# L3DCube_6x6x6_BaseBoard_Rev1_2.net
KiCad netlist of a schematic drawn in EAGLE
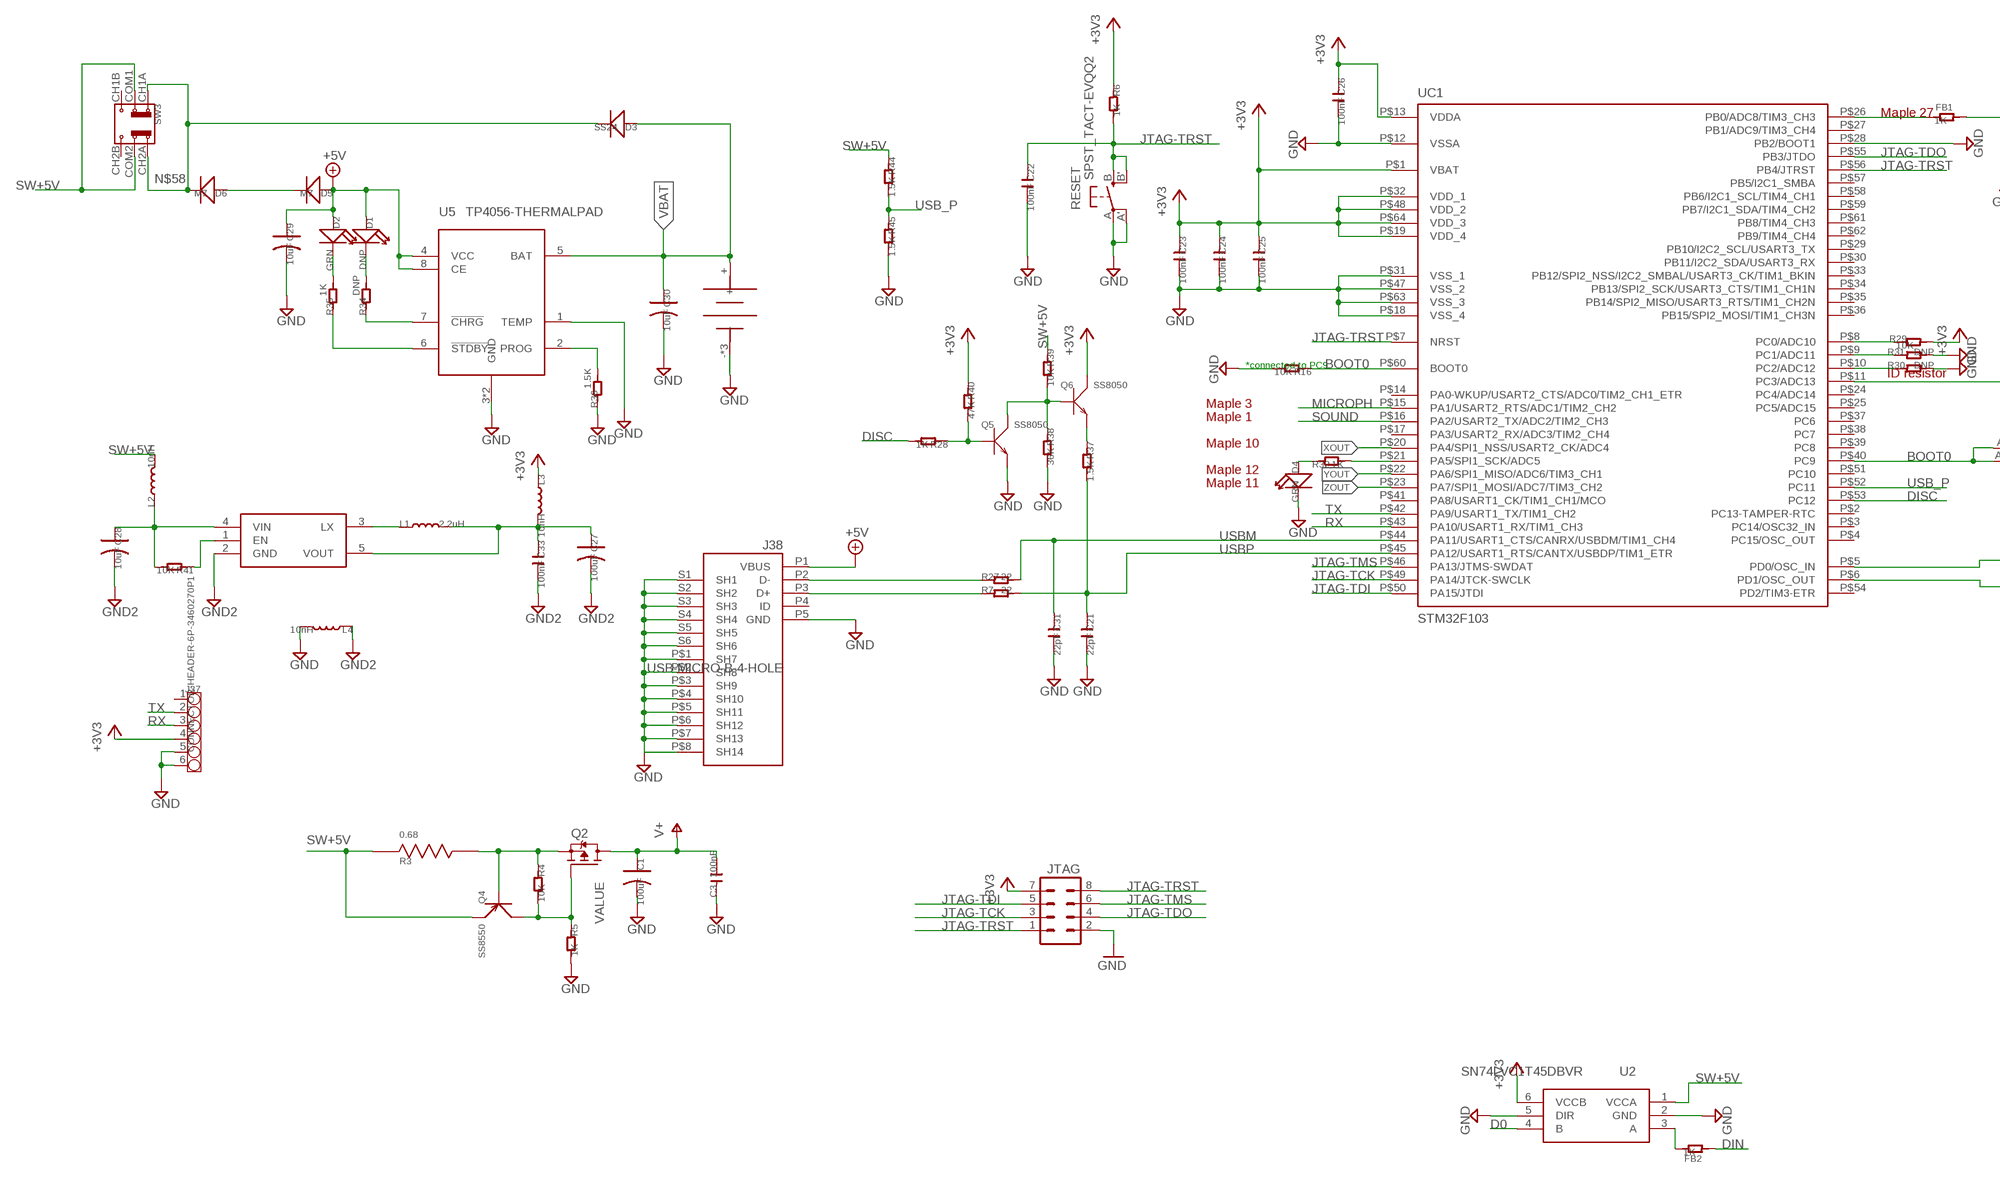
[diagram p0: schematic, sheet 1, part 1 of 2]
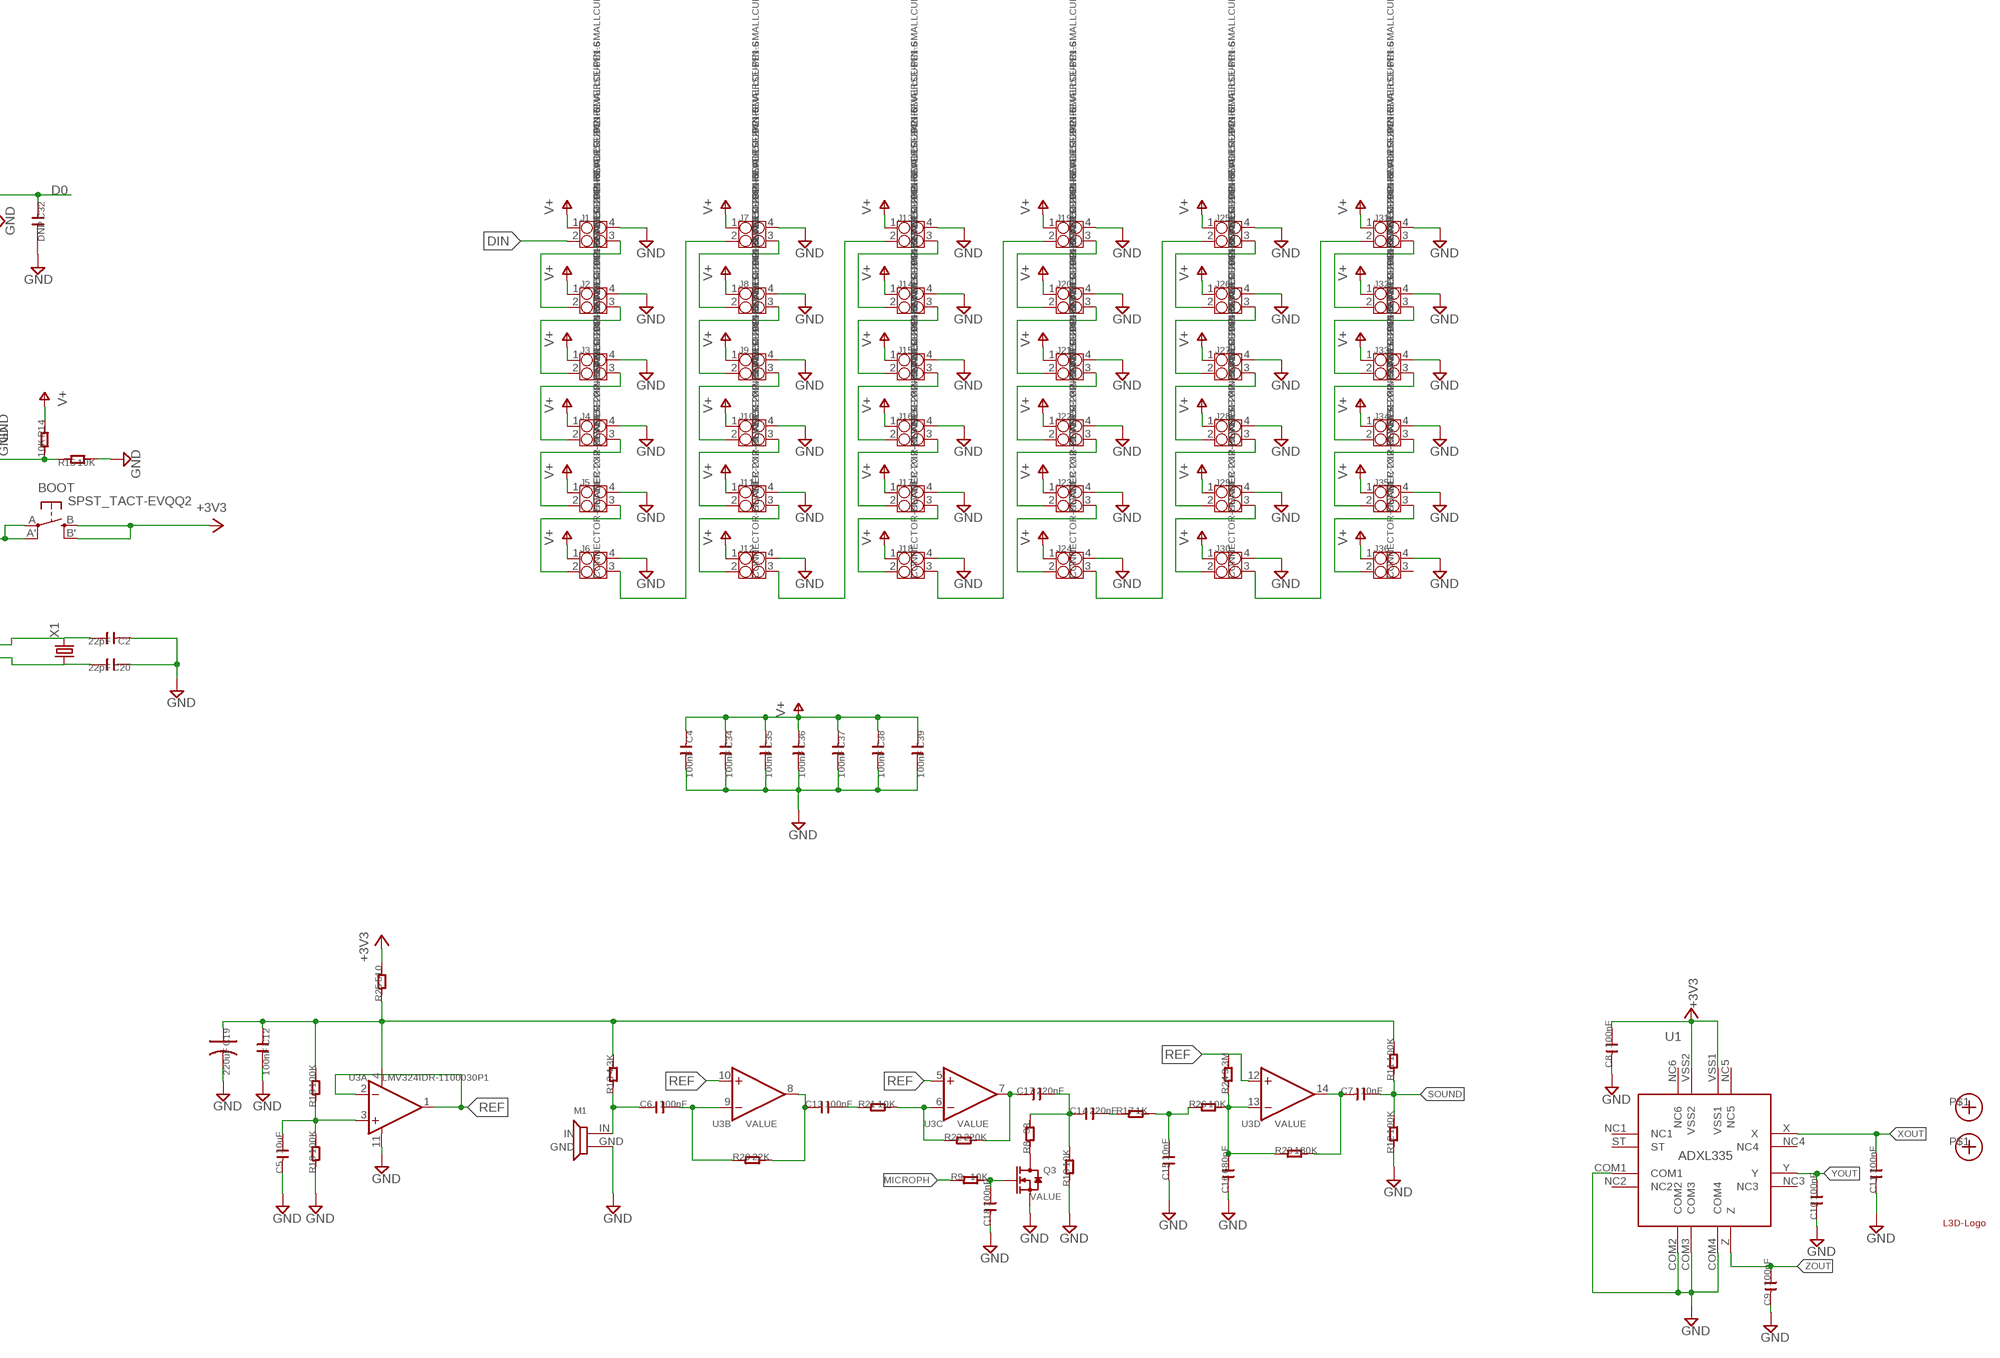
[diagram p1: schematic, sheet 1, part 2 of 2]

(export (version "E")
  (design (tool "Eeschema 10.0.6"))
  (components
    (comp (ref "B1")
      (value "BATTERY")
      (footprint "eagle-import:2P-SMD-2.0-90D")
      (libsource (lib "eagle-import") (part "BATTERY"))
    )
    (comp (ref "BOOT")
      (value "SPST_TACT-EVQQ2")
      (footprint "eagle-import:EVQ-Q2")
      (libsource (lib "eagle-import") (part "SPST_TACT-EVQQ2"))
    )
    (comp (ref "C1")
      (value "100uF")
      (footprint "eagle-import:AVX-B")
      (libsource (lib "eagle-import") (part "C-POLAR-B"))
    )
    (comp (ref "C2")
      (value "22pF")
      (footprint "eagle-import:C0603")
      (libsource (lib "eagle-import") (part "C-0603"))
    )
    (comp (ref "C3")
      (value "100nF")
      (footprint "eagle-import:C0603")
      (libsource (lib "eagle-import") (part "C-0603"))
    )
    (comp (ref "C4")
      (value "100nF")
      (footprint "eagle-import:C0603")
      (libsource (lib "eagle-import") (part "C-0603"))
    )
    (comp (ref "C5")
      (value "10uF")
      (footprint "eagle-import:C0603")
      (libsource (lib "eagle-import") (part "C-0603"))
    )
    (comp (ref "C6")
      (value "100nF")
      (footprint "eagle-import:C0603")
      (libsource (lib "eagle-import") (part "C-0603"))
    )
    (comp (ref "C7")
      (value "10nF")
      (footprint "eagle-import:C0603")
      (libsource (lib "eagle-import") (part "C-0603"))
    )
    (comp (ref "C8")
      (value "100nF")
      (footprint "eagle-import:C0603")
      (libsource (lib "eagle-import") (part "C-0603"))
    )
    (comp (ref "C9")
      (value "100nF")
      (footprint "eagle-import:C0603")
      (libsource (lib "eagle-import") (part "C-0603"))
    )
    (comp (ref "C10")
      (value "100nF")
      (footprint "eagle-import:C0603")
      (libsource (lib "eagle-import") (part "C-0603"))
    )
    (comp (ref "C11")
      (value "100nF")
      (footprint "eagle-import:C0603")
      (libsource (lib "eagle-import") (part "C-0603"))
    )
    (comp (ref "C12")
      (value "100nF")
      (footprint "eagle-import:C0603")
      (libsource (lib "eagle-import") (part "C-0603"))
    )
    (comp (ref "C13")
      (value "100nF")
      (footprint "eagle-import:C0603")
      (libsource (lib "eagle-import") (part "C-0603"))
    )
    (comp (ref "C14")
      (value "220nF")
      (footprint "eagle-import:C0603")
      (libsource (lib "eagle-import") (part "C-0603"))
    )
    (comp (ref "C15")
      (value "10nF")
      (footprint "eagle-import:C0603")
      (libsource (lib "eagle-import") (part "C-0603"))
    )
    (comp (ref "C16")
      (value "680pF")
      (footprint "eagle-import:C0603")
      (libsource (lib "eagle-import") (part "C-0603"))
    )
    (comp (ref "C17")
      (value "220nF")
      (footprint "eagle-import:C0603")
      (libsource (lib "eagle-import") (part "C-0603"))
    )
    (comp (ref "C18")
      (value "100nF")
      (footprint "eagle-import:C0603")
      (libsource (lib "eagle-import") (part "C-0603"))
    )
    (comp (ref "C19")
      (value "220uF")
      (footprint "eagle-import:AVX-B")
      (libsource (lib "eagle-import") (part "C-POLAR-B"))
    )
    (comp (ref "C20")
      (value "22pF")
      (footprint "eagle-import:C0603")
      (libsource (lib "eagle-import") (part "C-0603"))
    )
    (comp (ref "C21")
      (value "22pF")
      (footprint "eagle-import:C0603")
      (libsource (lib "eagle-import") (part "C-0603"))
    )
    (comp (ref "C22")
      (value "100nF")
      (footprint "eagle-import:C0603")
      (libsource (lib "eagle-import") (part "C-0603"))
    )
    (comp (ref "C23")
      (value "100nF")
      (footprint "eagle-import:C0603")
      (libsource (lib "eagle-import") (part "C-0603"))
    )
    (comp (ref "C24")
      (value "100nF")
      (footprint "eagle-import:C0603")
      (libsource (lib "eagle-import") (part "C-0603"))
    )
    (comp (ref "C25")
      (value "100nF")
      (footprint "eagle-import:C0603")
      (libsource (lib "eagle-import") (part "C-0603"))
    )
    (comp (ref "C26")
      (value "100nF")
      (footprint "eagle-import:C0603")
      (libsource (lib "eagle-import") (part "C-0603"))
    )
    (comp (ref "C27")
      (value "100uF")
      (footprint "eagle-import:AVX-B")
      (libsource (lib "eagle-import") (part "C-POLAR-B"))
    )
    (comp (ref "C28")
      (value "10uF")
      (footprint "eagle-import:AVX-A")
      (libsource (lib "eagle-import") (part "C-POLAR-A"))
    )
    (comp (ref "C29")
      (value "10uF")
      (footprint "eagle-import:AVX-A")
      (libsource (lib "eagle-import") (part "C-POLAR-A"))
    )
    (comp (ref "C30")
      (value "10uF")
      (footprint "eagle-import:AVX-A")
      (libsource (lib "eagle-import") (part "C-POLAR-A"))
    )
    (comp (ref "C31")
      (value "22pF")
      (footprint "eagle-import:C0603")
      (libsource (lib "eagle-import") (part "C-0603"))
    )
    (comp (ref "C32")
      (value "DNP")
      (footprint "eagle-import:C0603")
      (libsource (lib "eagle-import") (part "C-0603"))
    )
    (comp (ref "C33")
      (value "100nF")
      (footprint "eagle-import:C0603")
      (libsource (lib "eagle-import") (part "C-0603"))
    )
    (comp (ref "C34")
      (value "100nF")
      (footprint "eagle-import:C0603")
      (libsource (lib "eagle-import") (part "C-0603"))
    )
    (comp (ref "C35")
      (value "100nF")
      (footprint "eagle-import:C0603")
      (libsource (lib "eagle-import") (part "C-0603"))
    )
    (comp (ref "C36")
      (value "100nF")
      (footprint "eagle-import:C0603")
      (libsource (lib "eagle-import") (part "C-0603"))
    )
    (comp (ref "C37")
      (value "100nF")
      (footprint "eagle-import:C0603")
      (libsource (lib "eagle-import") (part "C-0603"))
    )
    (comp (ref "C38")
      (value "100nF")
      (footprint "eagle-import:C0603")
      (libsource (lib "eagle-import") (part "C-0603"))
    )
    (comp (ref "C39")
      (value "100nF")
      (footprint "eagle-import:C0603")
      (libsource (lib "eagle-import") (part "C-0603"))
    )
    (comp (ref "D1")
      (value "DNP")
      (footprint "eagle-import:LED0603")
      (libsource (lib "eagle-import") (part "LED"))
    )
    (comp (ref "D2")
      (value "GRN")
      (footprint "eagle-import:LED0603")
      (libsource (lib "eagle-import") (part "LED"))
    )
    (comp (ref "D3")
      (value "SS24")
      (footprint "eagle-import:SMB")
      (libsource (lib "eagle-import") (part "D-SMB"))
    )
    (comp (ref "D4")
      (value "GRN")
      (footprint "eagle-import:LED0603")
      (libsource (lib "eagle-import") (part "LED"))
    )
    (comp (ref "D5")
      (value "M7")
      (footprint "eagle-import:DO-214AC")
      (libsource (lib "eagle-import") (part "D-SMA"))
    )
    (comp (ref "D6")
      (value "M7")
      (footprint "eagle-import:DO-214AC")
      (libsource (lib "eagle-import") (part "D-SMA"))
    )
    (comp (ref "FB1")
      (value "1K")
      (footprint "eagle-import:R0603")
      (libsource (lib "eagle-import") (part "R-0603"))
    )
    (comp (ref "FB2")
      (value "1K")
      (footprint "eagle-import:R0603")
      (libsource (lib "eagle-import") (part "R-0603"))
    )
    (comp (ref "J1")
      (value "CONNECTOR-HEADER-2X2-REVERSE-PIN-SMALLCUBE1.6")
      (footprint "eagle-import:2X2P-2.54-6X6X6-CUBE-TH")
      (libsource (lib "eagle-import") (part "CONNECTOR-HEADER-2X2-REVERSE-PIN-SMALLCUBE1.6"))
    )
    (comp (ref "J2")
      (value "CONNECTOR-HEADER-2X2-REVERSE-PIN-SMALLCUBE1.6")
      (footprint "eagle-import:2X2P-2.54-6X6X6-CUBE-TH")
      (libsource (lib "eagle-import") (part "CONNECTOR-HEADER-2X2-REVERSE-PIN-SMALLCUBE1.6"))
    )
    (comp (ref "J3")
      (value "CONNECTOR-HEADER-2X2-REVERSE-PIN-SMALLCUBE1.6")
      (footprint "eagle-import:2X2P-2.54-6X6X6-CUBE-TH")
      (libsource (lib "eagle-import") (part "CONNECTOR-HEADER-2X2-REVERSE-PIN-SMALLCUBE1.6"))
    )
    (comp (ref "J4")
      (value "CONNECTOR-HEADER-2X2-REVERSE-PIN-SMALLCUBE1.6")
      (footprint "eagle-import:2X2P-2.54-6X6X6-CUBE-TH")
      (libsource (lib "eagle-import") (part "CONNECTOR-HEADER-2X2-REVERSE-PIN-SMALLCUBE1.6"))
    )
    (comp (ref "J5")
      (value "CONNECTOR-HEADER-2X2-REVERSE-PIN-SMALLCUBE1.6")
      (footprint "eagle-import:2X2P-2.54-6X6X6-CUBE-TH")
      (libsource (lib "eagle-import") (part "CONNECTOR-HEADER-2X2-REVERSE-PIN-SMALLCUBE1.6"))
    )
    (comp (ref "J6")
      (value "CONNECTOR-HEADER-2X2-REVERSE-PIN-SMALLCUBE1.6")
      (footprint "eagle-import:2X2P-2.54-6X6X6-CUBE-TH")
      (libsource (lib "eagle-import") (part "CONNECTOR-HEADER-2X2-REVERSE-PIN-SMALLCUBE1.6"))
    )
    (comp (ref "J7")
      (value "CONNECTOR-HEADER-2X2-REVERSE-PIN-SMALLCUBE1.6")
      (footprint "eagle-import:2X2P-2.54-6X6X6-CUBE-TH")
      (libsource (lib "eagle-import") (part "CONNECTOR-HEADER-2X2-REVERSE-PIN-SMALLCUBE1.6"))
    )
    (comp (ref "J8")
      (value "CONNECTOR-HEADER-2X2-REVERSE-PIN-SMALLCUBE1.6")
      (footprint "eagle-import:2X2P-2.54-6X6X6-CUBE-TH")
      (libsource (lib "eagle-import") (part "CONNECTOR-HEADER-2X2-REVERSE-PIN-SMALLCUBE1.6"))
    )
    (comp (ref "J9")
      (value "CONNECTOR-HEADER-2X2-REVERSE-PIN-SMALLCUBE1.6")
      (footprint "eagle-import:2X2P-2.54-6X6X6-CUBE-TH")
      (libsource (lib "eagle-import") (part "CONNECTOR-HEADER-2X2-REVERSE-PIN-SMALLCUBE1.6"))
    )
    (comp (ref "J10")
      (value "CONNECTOR-HEADER-2X2-REVERSE-PIN-SMALLCUBE1.6")
      (footprint "eagle-import:2X2P-2.54-6X6X6-CUBE-TH")
      (libsource (lib "eagle-import") (part "CONNECTOR-HEADER-2X2-REVERSE-PIN-SMALLCUBE1.6"))
    )
    (comp (ref "J11")
      (value "CONNECTOR-HEADER-2X2-REVERSE-PIN-SMALLCUBE1.6")
      (footprint "eagle-import:2X2P-2.54-6X6X6-CUBE-TH")
      (libsource (lib "eagle-import") (part "CONNECTOR-HEADER-2X2-REVERSE-PIN-SMALLCUBE1.6"))
    )
    (comp (ref "J12")
      (value "CONNECTOR-HEADER-2X2-REVERSE-PIN-SMALLCUBE1.6")
      (footprint "eagle-import:2X2P-2.54-6X6X6-CUBE-TH")
      (libsource (lib "eagle-import") (part "CONNECTOR-HEADER-2X2-REVERSE-PIN-SMALLCUBE1.6"))
    )
    (comp (ref "J13")
      (value "CONNECTOR-HEADER-2X2-REVERSE-PIN-SMALLCUBE1.6")
      (footprint "eagle-import:2X2P-2.54-6X6X6-CUBE-TH")
      (libsource (lib "eagle-import") (part "CONNECTOR-HEADER-2X2-REVERSE-PIN-SMALLCUBE1.6"))
    )
    (comp (ref "J14")
      (value "CONNECTOR-HEADER-2X2-REVERSE-PIN-SMALLCUBE1.6")
      (footprint "eagle-import:2X2P-2.54-6X6X6-CUBE-TH")
      (libsource (lib "eagle-import") (part "CONNECTOR-HEADER-2X2-REVERSE-PIN-SMALLCUBE1.6"))
    )
    (comp (ref "J15")
      (value "CONNECTOR-HEADER-2X2-REVERSE-PIN-SMALLCUBE1.6")
      (footprint "eagle-import:2X2P-2.54-6X6X6-CUBE-TH")
      (libsource (lib "eagle-import") (part "CONNECTOR-HEADER-2X2-REVERSE-PIN-SMALLCUBE1.6"))
    )
    (comp (ref "J16")
      (value "CONNECTOR-HEADER-2X2-REVERSE-PIN-SMALLCUBE1.6")
      (footprint "eagle-import:2X2P-2.54-6X6X6-CUBE-TH")
      (libsource (lib "eagle-import") (part "CONNECTOR-HEADER-2X2-REVERSE-PIN-SMALLCUBE1.6"))
    )
    (comp (ref "J17")
      (value "CONNECTOR-HEADER-2X2-REVERSE-PIN-SMALLCUBE1.6")
      (footprint "eagle-import:2X2P-2.54-6X6X6-CUBE-TH")
      (libsource (lib "eagle-import") (part "CONNECTOR-HEADER-2X2-REVERSE-PIN-SMALLCUBE1.6"))
    )
    (comp (ref "J18")
      (value "CONNECTOR-HEADER-2X2-REVERSE-PIN-SMALLCUBE1.6")
      (footprint "eagle-import:2X2P-2.54-6X6X6-CUBE-TH")
      (libsource (lib "eagle-import") (part "CONNECTOR-HEADER-2X2-REVERSE-PIN-SMALLCUBE1.6"))
    )
    (comp (ref "J19")
      (value "CONNECTOR-HEADER-2X2-REVERSE-PIN-SMALLCUBE1.6")
      (footprint "eagle-import:2X2P-2.54-6X6X6-CUBE-TH")
      (libsource (lib "eagle-import") (part "CONNECTOR-HEADER-2X2-REVERSE-PIN-SMALLCUBE1.6"))
    )
    (comp (ref "J20")
      (value "CONNECTOR-HEADER-2X2-REVERSE-PIN-SMALLCUBE1.6")
      (footprint "eagle-import:2X2P-2.54-6X6X6-CUBE-TH")
      (libsource (lib "eagle-import") (part "CONNECTOR-HEADER-2X2-REVERSE-PIN-SMALLCUBE1.6"))
    )
    (comp (ref "J21")
      (value "CONNECTOR-HEADER-2X2-REVERSE-PIN-SMALLCUBE1.6")
      (footprint "eagle-import:2X2P-2.54-6X6X6-CUBE-TH")
      (libsource (lib "eagle-import") (part "CONNECTOR-HEADER-2X2-REVERSE-PIN-SMALLCUBE1.6"))
    )
    (comp (ref "J22")
      (value "CONNECTOR-HEADER-2X2-REVERSE-PIN-SMALLCUBE1.6")
      (footprint "eagle-import:2X2P-2.54-6X6X6-CUBE-TH")
      (libsource (lib "eagle-import") (part "CONNECTOR-HEADER-2X2-REVERSE-PIN-SMALLCUBE1.6"))
    )
    (comp (ref "J23")
      (value "CONNECTOR-HEADER-2X2-REVERSE-PIN-SMALLCUBE1.6")
      (footprint "eagle-import:2X2P-2.54-6X6X6-CUBE-TH")
      (libsource (lib "eagle-import") (part "CONNECTOR-HEADER-2X2-REVERSE-PIN-SMALLCUBE1.6"))
    )
    (comp (ref "J24")
      (value "CONNECTOR-HEADER-2X2-REVERSE-PIN-SMALLCUBE1.6")
      (footprint "eagle-import:2X2P-2.54-6X6X6-CUBE-TH")
      (libsource (lib "eagle-import") (part "CONNECTOR-HEADER-2X2-REVERSE-PIN-SMALLCUBE1.6"))
    )
    (comp (ref "J25")
      (value "CONNECTOR-HEADER-2X2-REVERSE-PIN-SMALLCUBE1.6")
      (footprint "eagle-import:2X2P-2.54-6X6X6-CUBE-TH")
      (libsource (lib "eagle-import") (part "CONNECTOR-HEADER-2X2-REVERSE-PIN-SMALLCUBE1.6"))
    )
    (comp (ref "J26")
      (value "CONNECTOR-HEADER-2X2-REVERSE-PIN-SMALLCUBE1.6")
      (footprint "eagle-import:2X2P-2.54-6X6X6-CUBE-TH")
      (libsource (lib "eagle-import") (part "CONNECTOR-HEADER-2X2-REVERSE-PIN-SMALLCUBE1.6"))
    )
    (comp (ref "J27")
      (value "CONNECTOR-HEADER-2X2-REVERSE-PIN-SMALLCUBE1.6")
      (footprint "eagle-import:2X2P-2.54-6X6X6-CUBE-TH")
      (libsource (lib "eagle-import") (part "CONNECTOR-HEADER-2X2-REVERSE-PIN-SMALLCUBE1.6"))
    )
    (comp (ref "J28")
      (value "CONNECTOR-HEADER-2X2-REVERSE-PIN-SMALLCUBE1.6")
      (footprint "eagle-import:2X2P-2.54-6X6X6-CUBE-TH")
      (libsource (lib "eagle-import") (part "CONNECTOR-HEADER-2X2-REVERSE-PIN-SMALLCUBE1.6"))
    )
    (comp (ref "J29")
      (value "CONNECTOR-HEADER-2X2-REVERSE-PIN-SMALLCUBE1.6")
      (footprint "eagle-import:2X2P-2.54-6X6X6-CUBE-TH")
      (libsource (lib "eagle-import") (part "CONNECTOR-HEADER-2X2-REVERSE-PIN-SMALLCUBE1.6"))
    )
    (comp (ref "J30")
      (value "CONNECTOR-HEADER-2X2-REVERSE-PIN-SMALLCUBE1.6")
      (footprint "eagle-import:2X2P-2.54-6X6X6-CUBE-TH")
      (libsource (lib "eagle-import") (part "CONNECTOR-HEADER-2X2-REVERSE-PIN-SMALLCUBE1.6"))
    )
    (comp (ref "J31")
      (value "CONNECTOR-HEADER-2X2-REVERSE-PIN-SMALLCUBE1.6")
      (footprint "eagle-import:2X2P-2.54-6X6X6-CUBE-TH")
      (libsource (lib "eagle-import") (part "CONNECTOR-HEADER-2X2-REVERSE-PIN-SMALLCUBE1.6"))
    )
    (comp (ref "J32")
      (value "CONNECTOR-HEADER-2X2-REVERSE-PIN-SMALLCUBE1.6")
      (footprint "eagle-import:2X2P-2.54-6X6X6-CUBE-TH")
      (libsource (lib "eagle-import") (part "CONNECTOR-HEADER-2X2-REVERSE-PIN-SMALLCUBE1.6"))
    )
    (comp (ref "J33")
      (value "CONNECTOR-HEADER-2X2-REVERSE-PIN-SMALLCUBE1.6")
      (footprint "eagle-import:2X2P-2.54-6X6X6-CUBE-TH")
      (libsource (lib "eagle-import") (part "CONNECTOR-HEADER-2X2-REVERSE-PIN-SMALLCUBE1.6"))
    )
    (comp (ref "J34")
      (value "CONNECTOR-HEADER-2X2-REVERSE-PIN-SMALLCUBE1.6")
      (footprint "eagle-import:2X2P-2.54-6X6X6-CUBE-TH")
      (libsource (lib "eagle-import") (part "CONNECTOR-HEADER-2X2-REVERSE-PIN-SMALLCUBE1.6"))
    )
    (comp (ref "J35")
      (value "CONNECTOR-HEADER-2X2-REVERSE-PIN-SMALLCUBE1.6")
      (footprint "eagle-import:2X2P-2.54-6X6X6-CUBE-TH")
      (libsource (lib "eagle-import") (part "CONNECTOR-HEADER-2X2-REVERSE-PIN-SMALLCUBE1.6"))
    )
    (comp (ref "J36")
      (value "CONNECTOR-HEADER-2X2-REVERSE-PIN-SMALLCUBE1.6")
      (footprint "eagle-import:2X2P-2.54-6X6X6-CUBE-TH")
      (libsource (lib "eagle-import") (part "CONNECTOR-HEADER-2X2-REVERSE-PIN-SMALLCUBE1.6"))
    )
    (comp (ref "J37")
      (value "CONNECTOR-HEADER-6P-3460270P1")
      (footprint "eagle-import:1X6P-2.54-8.5-BLACK-FEMALE")
      (libsource (lib "eagle-import") (part "CONNECTOR-HEADER-6P-3460270P1"))
    )
    (comp (ref "J38")
      (value "USB-MICRO-B-4-HOLE")
      (footprint "eagle-import:CON2_USB_MICRO_B_AT")
      (libsource (lib "eagle-import") (part "USB-MICRO-B-4-HOLE"))
    )
    (comp (ref "JTAG")
      (value "MA04-2")
      (footprint "eagle-import:MA04-2")
      (libsource (lib "eagle-import") (part "MA04-2"))
    )
    (comp (ref "L1")
      (value "2.2uH")
      (footprint "eagle-import:L0420")
      (libsource (lib "eagle-import") (part "L-SPD3D16-4R7M"))
    )
    (comp (ref "L2")
      (value "10nH")
      (footprint "eagle-import:L0603")
      (libsource (lib "eagle-import") (part "L-0603"))
    )
    (comp (ref "L3")
      (value "10nH")
      (footprint "eagle-import:L0603")
      (libsource (lib "eagle-import") (part "L-0603"))
    )
    (comp (ref "L4")
      (value "10nH")
      (footprint "eagle-import:L0603")
      (libsource (lib "eagle-import") (part "L-0603"))
    )
    (comp (ref "M1")
      (value "MICROPHONE")
      (footprint "eagle-import:MICROPHONE")
      (libsource (lib "eagle-import") (part "MICROPHONE"))
    )
    (comp (ref "Q2")
      (value "FDD6637")
      (footprint "eagle-import:TO252")
      (libsource (lib "eagle-import") (part "FDD4141TO252"))
    )
    (comp (ref "Q3")
      (value "2N7002")
      (footprint "eagle-import:SOT23")
      (libsource (lib "eagle-import") (part "MOSFET-N-044020001"))
    )
    (comp (ref "Q4")
      (value "SS8550")
      (footprint "eagle-import:SOT23")
      (libsource (lib "eagle-import") (part "TRANSISTOR-PNP-041003001"))
    )
    (comp (ref "Q5")
      (value "SS8050")
      (footprint "eagle-import:SOT23")
      (libsource (lib "eagle-import") (part "TRANSISTOR-NPN-0400000P1"))
    )
    (comp (ref "Q6")
      (value "SS8050")
      (footprint "eagle-import:SOT23")
      (libsource (lib "eagle-import") (part "TRANSISTOR-NPN-0400000P1"))
    )
    (comp (ref "R3")
      (value "0.68")
      (footprint "eagle-import:RESISTOR-3W-20MM")
      (libsource (lib "eagle-import") (part "RESISTOR-3W-20MM"))
    )
    (comp (ref "R4")
      (value "10K")
      (footprint "eagle-import:R0603")
      (libsource (lib "eagle-import") (part "R-0603"))
    )
    (comp (ref "R5")
      (value "1K")
      (footprint "eagle-import:R0603")
      (libsource (lib "eagle-import") (part "R-0603"))
    )
    (comp (ref "R6")
      (value "1K")
      (footprint "eagle-import:R0603")
      (libsource (lib "eagle-import") (part "R-0603"))
    )
    (comp (ref "R7")
      (value "22")
      (footprint "eagle-import:R0603")
      (libsource (lib "eagle-import") (part "R-0603"))
    )
    (comp (ref "R8")
      (value "33")
      (footprint "eagle-import:R0603")
      (libsource (lib "eagle-import") (part "R-0603"))
    )
    (comp (ref "R9")
      (value "10K")
      (footprint "eagle-import:R0603")
      (libsource (lib "eagle-import") (part "R-0603"))
    )
    (comp (ref "R10")
      (value "10K")
      (footprint "eagle-import:R0603")
      (libsource (lib "eagle-import") (part "R-0603"))
    )
    (comp (ref "R11")
      (value "100K")
      (footprint "eagle-import:R0603")
      (libsource (lib "eagle-import") (part "R-0603"))
    )
    (comp (ref "R12")
      (value "100K")
      (footprint "eagle-import:R0603")
      (libsource (lib "eagle-import") (part "R-0603"))
    )
    (comp (ref "R13")
      (value "4.3K")
      (footprint "eagle-import:R0603")
      (libsource (lib "eagle-import") (part "R-0603"))
    )
    (comp (ref "R14")
      (value "10K")
      (footprint "eagle-import:R0603")
      (libsource (lib "eagle-import") (part "R-0603"))
    )
    (comp (ref "R15")
      (value "10K")
      (footprint "eagle-import:R0603")
      (libsource (lib "eagle-import") (part "R-0603"))
    )
    (comp (ref "R16")
      (value "10K")
      (footprint "eagle-import:R0603")
      (libsource (lib "eagle-import") (part "R-0603"))
    )
    (comp (ref "R17")
      (value "1K")
      (footprint "eagle-import:R0603")
      (libsource (lib "eagle-import") (part "R-0603"))
    )
    (comp (ref "R18")
      (value "100K")
      (footprint "eagle-import:R0603")
      (libsource (lib "eagle-import") (part "R-0603"))
    )
    (comp (ref "R19")
      (value "100K")
      (footprint "eagle-import:R0603")
      (libsource (lib "eagle-import") (part "R-0603"))
    )
    (comp (ref "R20")
      (value "22K")
      (footprint "eagle-import:R0603")
      (libsource (lib "eagle-import") (part "R-0603"))
    )
    (comp (ref "R21")
      (value "10K")
      (footprint "eagle-import:R0603")
      (libsource (lib "eagle-import") (part "R-0603"))
    )
    (comp (ref "R22")
      (value "220K")
      (footprint "eagle-import:R0603")
      (libsource (lib "eagle-import") (part "R-0603"))
    )
    (comp (ref "R23")
      (value "180K")
      (footprint "eagle-import:R0603")
      (libsource (lib "eagle-import") (part "R-0603"))
    )
    (comp (ref "R24")
      (value "3.3M")
      (footprint "eagle-import:R0603")
      (libsource (lib "eagle-import") (part "R-0603"))
    )
    (comp (ref "R25")
      (value "510")
      (footprint "eagle-import:R0603")
      (libsource (lib "eagle-import") (part "R-0603"))
    )
    (comp (ref "R26")
      (value "10K")
      (footprint "eagle-import:R0603")
      (libsource (lib "eagle-import") (part "R-0603"))
    )
    (comp (ref "R27")
      (value "22")
      (footprint "eagle-import:R0603")
      (libsource (lib "eagle-import") (part "R-0603"))
    )
    (comp (ref "R28")
      (value "1K")
      (footprint "eagle-import:R0603")
      (libsource (lib "eagle-import") (part "R-0603"))
    )
    (comp (ref "R29")
      (value "10K")
      (footprint "eagle-import:R0603")
      (libsource (lib "eagle-import") (part "R-0603"))
    )
    (comp (ref "R30")
      (value "DNP")
      (footprint "eagle-import:R0603")
      (libsource (lib "eagle-import") (part "R-0603"))
    )
    (comp (ref "R31")
      (value "DNP")
      (footprint "eagle-import:R0603")
      (libsource (lib "eagle-import") (part "R-0603"))
    )
    (comp (ref "R32")
      (value "1K")
      (footprint "eagle-import:R0603")
      (libsource (lib "eagle-import") (part "R-0603"))
    )
    (comp (ref "R34")
      (value "DNP")
      (footprint "eagle-import:R0603")
      (libsource (lib "eagle-import") (part "R-0603"))
    )
    (comp (ref "R35")
      (value "1K")
      (footprint "eagle-import:R0603")
      (libsource (lib "eagle-import") (part "R-0603"))
    )
    (comp (ref "R36")
      (value "1.5K")
      (footprint "eagle-import:R0603")
      (libsource (lib "eagle-import") (part "R-0603"))
    )
    (comp (ref "R37")
      (value "1.5K")
      (footprint "eagle-import:R0603")
      (libsource (lib "eagle-import") (part "R-0603"))
    )
    (comp (ref "R38")
      (value "36K")
      (footprint "eagle-import:R0603")
      (libsource (lib "eagle-import") (part "R-0603"))
    )
    (comp (ref "R39")
      (value "10K")
      (footprint "eagle-import:R0603")
      (libsource (lib "eagle-import") (part "R-0603"))
    )
    (comp (ref "R40")
      (value "47K")
      (footprint "eagle-import:R0603")
      (libsource (lib "eagle-import") (part "R-0603"))
    )
    (comp (ref "R41")
      (value "10K")
      (footprint "eagle-import:R0402")
      (libsource (lib "eagle-import") (part "R-0402"))
    )
    (comp (ref "R44")
      (value "1.5K")
      (footprint "eagle-import:R0603")
      (libsource (lib "eagle-import") (part "R-0603"))
    )
    (comp (ref "R45")
      (value "1.5K")
      (footprint "eagle-import:R0603")
      (libsource (lib "eagle-import") (part "R-0603"))
    )
    (comp (ref "RESET")
      (value "SPST_TACT-EVQQ2")
      (footprint "eagle-import:EVQ-Q2")
      (libsource (lib "eagle-import") (part "SPST_TACT-EVQQ2"))
    )
    (comp (ref "SW3")
      (value "SWITCH-22D02")
      (footprint "eagle-import:SWITCH-22D02")
      (libsource (lib "eagle-import") (part "SWITCH-22D02"))
    )
    (comp (ref "U$1")
      (value "L3D-LOGOL3DCUBE-LOGO-0.8X2.5")
      (footprint "eagle-import:L3DCUBE-LOGO-0.8X2.5")
      (libsource (lib "eagle-import") (part "L3D-LOGOL3DCUBE-LOGO-0.8X2.5"))
    )
    (comp (ref "U$2")
      (value "FIDUCIAL-MARK")
      (footprint "eagle-import:FIDUCIAL-MARK")
      (libsource (lib "eagle-import") (part "FIDUCIAL-MARK"))
    )
    (comp (ref "U$3")
      (value "FIDUCIAL-MARK")
      (footprint "eagle-import:FIDUCIAL-MARK")
      (libsource (lib "eagle-import") (part "FIDUCIAL-MARK"))
    )
    (comp (ref "U1")
      (value "ADXL335")
      (footprint "eagle-import:ADXL335")
      (libsource (lib "eagle-import") (part "ADXL335"))
    )
    (comp (ref "U2")
      (value "SN74LVC1T45DBVR")
      (footprint "eagle-import:SOT23-6")
      (libsource (lib "eagle-import") (part "SN74LVC1T45DBVR"))
    )
    (comp (ref "U3")
      (value "LMV324IDR-1100030P1")
      (footprint "eagle-import:SOIC14")
      (libsource (lib "eagle-import") (part "LMV324IDR-1100030P1"))
    )
    (comp (ref "U5")
      (value "TP4056-THERMALPAD")
      (footprint "eagle-import:SOIC8-PAD")
      (libsource (lib "eagle-import") (part "TP4056-THERMALPAD"))
    )
    (comp (ref "U11")
      (value "R8008-33")
      (footprint "eagle-import:SOT23-5")
      (libsource (lib "eagle-import") (part "R8008-33"))
    )
    (comp (ref "UC1")
      (value "STM32F103")
      (footprint "eagle-import:TQFP-10X10-64")
      (libsource (lib "eagle-import") (part "STM32F103"))
    )
    (comp (ref "X1")
      (value "CRYSTALSM49")
      (footprint "eagle-import:SM49")
      (libsource (lib "eagle-import") (part "CRYSTALSM49"))
    )
  )
  (nets
    (net (code "1") (name "+3V3") (class "Default")
      (node (ref "BOOT") (pin "B") (pinfunction "S_B") (pintype "passive"))
      (node (ref "BOOT") (pin "B'") (pinfunction "S1_B'") (pintype "passive"))
      (node (ref "C23") (pin "1") (pinfunction "1_1") (pintype "bidirectional"))
      (node (ref "C24") (pin "1") (pinfunction "1_1") (pintype "bidirectional"))
      (node (ref "C25") (pin "1") (pinfunction "1_1") (pintype "bidirectional"))
      (node (ref "C26") (pin "1") (pinfunction "1_1") (pintype "bidirectional"))
      (node (ref "C8") (pin "2") (pinfunction "2_2") (pintype "bidirectional"))
      (node (ref "J37") (pin "4") (pinfunction "4_4") (pintype "bidirectional"))
      (node (ref "JTAG") (pin "7") (pinfunction "7_7") (pintype "passive"))
      (node (ref "L3") (pin "1") (pinfunction "1_1") (pintype "passive"))
      (node (ref "Q6") (pin "3") (pinfunction "C_3") (pintype "passive"))
      (node (ref "R25") (pin "2") (pinfunction "2_2") (pintype "bidirectional"))
      (node (ref "R29") (pin "1") (pinfunction "1_1") (pintype "bidirectional"))
      (node (ref "R40") (pin "1") (pinfunction "1_1") (pintype "bidirectional"))
      (node (ref "R6") (pin "1") (pinfunction "1_1") (pintype "bidirectional"))
      (node (ref "U1") (pin "VSS1") (pinfunction "VSS1_VSS1") (pintype "bidirectional"))
      (node (ref "U1") (pin "VSS2") (pinfunction "VSS2_VSS2") (pintype "bidirectional"))
      (node (ref "U2") (pin "6") (pinfunction "VCCB_6") (pintype "bidirectional"))
      (node (ref "UC1") (pin "P$1") (pinfunction "VBAT_P$1") (pintype "power_in"))
      (node (ref "UC1") (pin "P$13") (pinfunction "VDDA_P$13") (pintype "power_in"))
      (node (ref "UC1") (pin "P$19") (pinfunction "VDD_4_P$19") (pintype "power_in"))
      (node (ref "UC1") (pin "P$32") (pinfunction "VDD_1_P$32") (pintype "power_in"))
      (node (ref "UC1") (pin "P$48") (pinfunction "VDD_2_P$48") (pintype "power_in"))
      (node (ref "UC1") (pin "P$64") (pinfunction "VDD_3_P$64") (pintype "power_in"))
    )
    (net (code "2") (name "+5V") (class "Default")
      (node (ref "C29") (pin "+") (pinfunction "1_+") (pintype "bidirectional"))
      (node (ref "D1") (pin "+") (pinfunction "+_+") (pintype "passive"))
      (node (ref "D2") (pin "+") (pinfunction "+_+") (pintype "passive"))
      (node (ref "D5") (pin "1") (pinfunction "+_1") (pintype "passive"))
      (node (ref "J38") (pin "P1") (pinfunction "VBUS_P1") (pintype "power_in"))
      (node (ref "U5") (pin "4") (pinfunction "VCC_4") (pintype "bidirectional"))
      (node (ref "U5") (pin "8") (pinfunction "CE_8") (pintype "bidirectional"))
    )
    (net (code "3") (name "/BOOT0") (class "Default")
      (node (ref "BOOT") (pin "A") (pinfunction "P_A") (pintype "passive"))
      (node (ref "BOOT") (pin "A'") (pinfunction "P1_A'") (pintype "passive"))
      (node (ref "R16") (pin "1") (pinfunction "1_1") (pintype "bidirectional"))
      (node (ref "UC1") (pin "P$40") (pinfunction "PC9_P$40") (pintype "bidirectional"))
      (node (ref "UC1") (pin "P$60") (pinfunction "BOOT0_P$60") (pintype "bidirectional"))
    )
    (net (code "4") (name "/D0") (class "Default")
      (node (ref "C32") (pin "1") (pinfunction "1_1") (pintype "bidirectional"))
      (node (ref "FB1") (pin "1") (pinfunction "1_1") (pintype "bidirectional"))
      (node (ref "U2") (pin "4") (pinfunction "B_4") (pintype "bidirectional"))
    )
    (net (code "5") (name "/DISC") (class "Default")
      (node (ref "R28") (pin "2") (pinfunction "2_2") (pintype "bidirectional"))
      (node (ref "UC1") (pin "P$53") (pinfunction "PC12_P$53") (pintype "bidirectional"))
    )
    (net (code "6") (name "/JTAG-TCK") (class "Default")
      (node (ref "JTAG") (pin "3") (pinfunction "3_3") (pintype "passive"))
      (node (ref "UC1") (pin "P$49") (pinfunction "PA14/JTCK-SWCLK_P$49") (pintype "bidirectional"))
    )
    (net (code "7") (name "/JTAG-TDI") (class "Default")
      (node (ref "JTAG") (pin "5") (pinfunction "5_5") (pintype "passive"))
      (node (ref "UC1") (pin "P$50") (pinfunction "PA15/JTDI_P$50") (pintype "bidirectional"))
    )
    (net (code "8") (name "/JTAG-TDO") (class "Default")
      (node (ref "JTAG") (pin "4") (pinfunction "4_4") (pintype "passive"))
      (node (ref "UC1") (pin "P$55") (pinfunction "PB3/JTDO_P$55") (pintype "bidirectional"))
    )
    (net (code "9") (name "/JTAG-TMS") (class "Default")
      (node (ref "JTAG") (pin "6") (pinfunction "6_6") (pintype "passive"))
      (node (ref "UC1") (pin "P$46") (pinfunction "PA13/JTMS-SWDAT_P$46") (pintype "bidirectional"))
    )
    (net (code "10") (name "/JTAG-TRST") (class "Default")
      (node (ref "C22") (pin "1") (pinfunction "1_1") (pintype "bidirectional"))
      (node (ref "JTAG") (pin "1") (pinfunction "1_1") (pintype "passive"))
      (node (ref "JTAG") (pin "8") (pinfunction "8_8") (pintype "passive"))
      (node (ref "R6") (pin "2") (pinfunction "2_2") (pintype "bidirectional"))
      (node (ref "RESET") (pin "B") (pinfunction "S_B") (pintype "passive"))
      (node (ref "RESET") (pin "B'") (pinfunction "S1_B'") (pintype "passive"))
      (node (ref "UC1") (pin "P$56") (pinfunction "PB4/JTRST_P$56") (pintype "bidirectional"))
      (node (ref "UC1") (pin "P$7") (pinfunction "NRST_P$7") (pintype "bidirectional"))
    )
    (net (code "11") (name "/N$58") (class "Default")
      (node (ref "D3") (pin "-") (pinfunction "-_-") (pintype "passive"))
      (node (ref "D6") (pin "2") (pinfunction "-_2") (pintype "passive"))
      (node (ref "SW3") (pin "CH1A") (pinfunction "CH1A_CH1A") (pintype "bidirectional"))
      (node (ref "SW3") (pin "CH2A") (pinfunction "CH2A_CH2A") (pintype "bidirectional"))
    )
    (net (code "12") (name "/RX") (class "Default")
      (node (ref "J37") (pin "3") (pinfunction "3_3") (pintype "bidirectional"))
      (node (ref "UC1") (pin "P$43") (pinfunction "PA10/USART1_RX/TIM1_CH3_P$43") (pintype "bidirectional"))
    )
    (net (code "13") (name "/SW+5V") (class "Default")
      (node (ref "L2") (pin "2") (pinfunction "2_2") (pintype "passive"))
      (node (ref "Q4") (pin "2") (pinfunction "E_2") (pintype "passive"))
      (node (ref "R3") (pin "1") (pinfunction "1_1") (pintype "bidirectional"))
      (node (ref "R39") (pin "1") (pinfunction "1_1") (pintype "bidirectional"))
      (node (ref "R44") (pin "1") (pinfunction "1_1") (pintype "bidirectional"))
      (node (ref "SW3") (pin "COM1") (pinfunction "COM1_COM1") (pintype "bidirectional"))
      (node (ref "SW3") (pin "COM2") (pinfunction "COM2_COM2") (pintype "bidirectional"))
      (node (ref "U2") (pin "1") (pinfunction "VCCA_1") (pintype "bidirectional"))
    )
    (net (code "14") (name "/TX") (class "Default")
      (node (ref "J37") (pin "2") (pinfunction "2_2") (pintype "bidirectional"))
      (node (ref "UC1") (pin "P$42") (pinfunction "PA9/USART1_TX/TIM1_CH2_P$42") (pintype "bidirectional"))
    )
    (net (code "15") (name "/USBM") (class "Default")
      (node (ref "C31") (pin "1") (pinfunction "1_1") (pintype "bidirectional"))
      (node (ref "R27") (pin "2") (pinfunction "2_2") (pintype "bidirectional"))
      (node (ref "UC1") (pin "P$44") (pinfunction "PA11/USART1_CTS/CANRX/USBDM/TIM1_CH4_P$44") (pintype "bidirectional"))
    )
    (net (code "16") (name "/USBP") (class "Default")
      (node (ref "C21") (pin "1") (pinfunction "1_1") (pintype "bidirectional"))
      (node (ref "R37") (pin "2") (pinfunction "2_2") (pintype "bidirectional"))
      (node (ref "R7") (pin "2") (pinfunction "2_2") (pintype "bidirectional"))
      (node (ref "UC1") (pin "P$45") (pinfunction "PA12/USART1_RTS/CANTX/USBDP/TIM1_ETR_P$45") (pintype "bidirectional"))
    )
    (net (code "17") (name "/USB_P") (class "Default")
      (node (ref "R44") (pin "2") (pinfunction "2_2") (pintype "bidirectional"))
      (node (ref "R45") (pin "1") (pinfunction "1_1") (pintype "bidirectional"))
      (node (ref "UC1") (pin "P$52") (pinfunction "PC11_P$52") (pintype "bidirectional"))
    )
    (net (code "18") (name "DIN") (class "Default")
      (node (ref "FB2") (pin "1") (pinfunction "1_1") (pintype "bidirectional"))
      (node (ref "J1") (pin "2") (pinfunction "2_2") (pintype "bidirectional"))
    )
    (net (code "19") (name "GND") (class "Default")
      (node (ref "B1") (pin "-") (pinfunction "-_-") (pintype "bidirectional"))
      (node (ref "B1") (pin "3") (pinfunction "-_3") (pintype "bidirectional"))
      (node (ref "B1") (pin "4") (pinfunction "-_4") (pintype "bidirectional"))
      (node (ref "C1") (pin "-") (pinfunction "2_-") (pintype "bidirectional"))
      (node (ref "C10") (pin "1") (pinfunction "1_1") (pintype "bidirectional"))
      (node (ref "C11") (pin "1") (pinfunction "1_1") (pintype "bidirectional"))
      (node (ref "C12") (pin "2") (pinfunction "2_2") (pintype "bidirectional"))
      (node (ref "C15") (pin "1") (pinfunction "1_1") (pintype "bidirectional"))
      (node (ref "C16") (pin "1") (pinfunction "1_1") (pintype "bidirectional"))
      (node (ref "C18") (pin "1") (pinfunction "1_1") (pintype "bidirectional"))
      (node (ref "C19") (pin "-") (pinfunction "2_-") (pintype "bidirectional"))
      (node (ref "C2") (pin "1") (pinfunction "1_1") (pintype "bidirectional"))
      (node (ref "C20") (pin "1") (pinfunction "1_1") (pintype "bidirectional"))
      (node (ref "C21") (pin "2") (pinfunction "2_2") (pintype "bidirectional"))
      (node (ref "C22") (pin "2") (pinfunction "2_2") (pintype "bidirectional"))
      (node (ref "C23") (pin "2") (pinfunction "2_2") (pintype "bidirectional"))
      (node (ref "C24") (pin "2") (pinfunction "2_2") (pintype "bidirectional"))
      (node (ref "C25") (pin "2") (pinfunction "2_2") (pintype "bidirectional"))
      (node (ref "C26") (pin "2") (pinfunction "2_2") (pintype "bidirectional"))
      (node (ref "C29") (pin "-") (pinfunction "2_-") (pintype "bidirectional"))
      (node (ref "C3") (pin "1") (pinfunction "1_1") (pintype "bidirectional"))
      (node (ref "C30") (pin "-") (pinfunction "2_-") (pintype "bidirectional"))
      (node (ref "C31") (pin "2") (pinfunction "2_2") (pintype "bidirectional"))
      (node (ref "C32") (pin "2") (pinfunction "2_2") (pintype "bidirectional"))
      (node (ref "C34") (pin "2") (pinfunction "2_2") (pintype "bidirectional"))
      (node (ref "C35") (pin "2") (pinfunction "2_2") (pintype "bidirectional"))
      (node (ref "C36") (pin "2") (pinfunction "2_2") (pintype "bidirectional"))
      (node (ref "C37") (pin "2") (pinfunction "2_2") (pintype "bidirectional"))
      (node (ref "C38") (pin "2") (pinfunction "2_2") (pintype "bidirectional"))
      (node (ref "C39") (pin "2") (pinfunction "2_2") (pintype "bidirectional"))
      (node (ref "C4") (pin "2") (pinfunction "2_2") (pintype "bidirectional"))
      (node (ref "C5") (pin "1") (pinfunction "1_1") (pintype "bidirectional"))
      (node (ref "C8") (pin "1") (pinfunction "1_1") (pintype "bidirectional"))
      (node (ref "C9") (pin "1") (pinfunction "1_1") (pintype "bidirectional"))
      (node (ref "D4") (pin "-") (pinfunction "-_-") (pintype "passive"))
      (node (ref "J1") (pin "4") (pinfunction "4_4") (pintype "bidirectional"))
      (node (ref "J10") (pin "4") (pinfunction "4_4") (pintype "bidirectional"))
      (node (ref "J11") (pin "4") (pinfunction "4_4") (pintype "bidirectional"))
      (node (ref "J12") (pin "4") (pinfunction "4_4") (pintype "bidirectional"))
      (node (ref "J13") (pin "4") (pinfunction "4_4") (pintype "bidirectional"))
      (node (ref "J14") (pin "4") (pinfunction "4_4") (pintype "bidirectional"))
      (node (ref "J15") (pin "4") (pinfunction "4_4") (pintype "bidirectional"))
      (node (ref "J16") (pin "4") (pinfunction "4_4") (pintype "bidirectional"))
      (node (ref "J17") (pin "4") (pinfunction "4_4") (pintype "bidirectional"))
      (node (ref "J18") (pin "4") (pinfunction "4_4") (pintype "bidirectional"))
      (node (ref "J19") (pin "4") (pinfunction "4_4") (pintype "bidirectional"))
      (node (ref "J2") (pin "4") (pinfunction "4_4") (pintype "bidirectional"))
      (node (ref "J20") (pin "4") (pinfunction "4_4") (pintype "bidirectional"))
      (node (ref "J21") (pin "4") (pinfunction "4_4") (pintype "bidirectional"))
      (node (ref "J22") (pin "4") (pinfunction "4_4") (pintype "bidirectional"))
      (node (ref "J23") (pin "4") (pinfunction "4_4") (pintype "bidirectional"))
      (node (ref "J24") (pin "4") (pinfunction "4_4") (pintype "bidirectional"))
      (node (ref "J25") (pin "4") (pinfunction "4_4") (pintype "bidirectional"))
      (node (ref "J26") (pin "4") (pinfunction "4_4") (pintype "bidirectional"))
      (node (ref "J27") (pin "4") (pinfunction "4_4") (pintype "bidirectional"))
      (node (ref "J28") (pin "4") (pinfunction "4_4") (pintype "bidirectional"))
      (node (ref "J29") (pin "4") (pinfunction "4_4") (pintype "bidirectional"))
      (node (ref "J3") (pin "4") (pinfunction "4_4") (pintype "bidirectional"))
      (node (ref "J30") (pin "4") (pinfunction "4_4") (pintype "bidirectional"))
      (node (ref "J31") (pin "4") (pinfunction "4_4") (pintype "bidirectional"))
      (node (ref "J32") (pin "4") (pinfunction "4_4") (pintype "bidirectional"))
      (node (ref "J33") (pin "4") (pinfunction "4_4") (pintype "bidirectional"))
      (node (ref "J34") (pin "4") (pinfunction "4_4") (pintype "bidirectional"))
      (node (ref "J35") (pin "4") (pinfunction "4_4") (pintype "bidirectional"))
      (node (ref "J36") (pin "4") (pinfunction "4_4") (pintype "bidirectional"))
      (node (ref "J37") (pin "5") (pinfunction "5_5") (pintype "bidirectional"))
      (node (ref "J37") (pin "6") (pinfunction "6_6") (pintype "bidirectional"))
      (node (ref "J38") (pin "P$1") (pinfunction "SH7_P$1") (pintype "passive"))
      (node (ref "J38") (pin "P$2") (pinfunction "SH8_P$2") (pintype "passive"))
      (node (ref "J38") (pin "P$3") (pinfunction "SH9_P$3") (pintype "passive"))
      (node (ref "J38") (pin "P$4") (pinfunction "SH10_P$4") (pintype "passive"))
      (node (ref "J38") (pin "P$5") (pinfunction "SH11_P$5") (pintype "passive"))
      (node (ref "J38") (pin "P$6") (pinfunction "SH12_P$6") (pintype "passive"))
      (node (ref "J38") (pin "P$7") (pinfunction "SH13_P$7") (pintype "passive"))
      (node (ref "J38") (pin "P$8") (pinfunction "SH14_P$8") (pintype "passive"))
      (node (ref "J38") (pin "P5") (pinfunction "GND_P5") (pintype "passive"))
      (node (ref "J38") (pin "S1") (pinfunction "SH1_S1") (pintype "passive"))
      (node (ref "J38") (pin "S2") (pinfunction "SH2_S2") (pintype "passive"))
      (node (ref "J38") (pin "S3") (pinfunction "SH3_S3") (pintype "passive"))
      (node (ref "J38") (pin "S4") (pinfunction "SH4_S4") (pintype "passive"))
      (node (ref "J38") (pin "S5") (pinfunction "SH5_S5") (pintype "passive"))
      (node (ref "J38") (pin "S6") (pinfunction "SH6_S6") (pintype "passive"))
      (node (ref "J4") (pin "4") (pinfunction "4_4") (pintype "bidirectional"))
      (node (ref "J5") (pin "4") (pinfunction "4_4") (pintype "bidirectional"))
      (node (ref "J6") (pin "4") (pinfunction "4_4") (pintype "bidirectional"))
      (node (ref "J7") (pin "4") (pinfunction "4_4") (pintype "bidirectional"))
      (node (ref "J8") (pin "4") (pinfunction "4_4") (pintype "bidirectional"))
      (node (ref "J9") (pin "4") (pinfunction "4_4") (pintype "bidirectional"))
      (node (ref "JTAG") (pin "2") (pinfunction "2_2") (pintype "passive"))
      (node (ref "L4") (pin "2") (pinfunction "2_2") (pintype "passive"))
      (node (ref "M1") (pin "GND") (pinfunction "GND_GND") (pintype "bidirectional"))
      (node (ref "Q3") (pin "2") (pinfunction "S_2") (pintype "passive"))
      (node (ref "Q5") (pin "2") (pinfunction "E_2") (pintype "passive"))
      (node (ref "R10") (pin "1") (pinfunction "1_1") (pintype "bidirectional"))
      (node (ref "R12") (pin "1") (pinfunction "1_1") (pintype "bidirectional"))
      (node (ref "R15") (pin "2") (pinfunction "2_2") (pintype "bidirectional"))
      (node (ref "R16") (pin "2") (pinfunction "2_2") (pintype "bidirectional"))
      (node (ref "R19") (pin "1") (pinfunction "1_1") (pintype "bidirectional"))
      (node (ref "R30") (pin "2") (pinfunction "2_2") (pintype "bidirectional"))
      (node (ref "R31") (pin "2") (pinfunction "2_2") (pintype "bidirectional"))
      (node (ref "R36") (pin "1") (pinfunction "1_1") (pintype "bidirectional"))
      (node (ref "R38") (pin "2") (pinfunction "2_2") (pintype "bidirectional"))
      (node (ref "R45") (pin "2") (pinfunction "2_2") (pintype "bidirectional"))
      (node (ref "R5") (pin "2") (pinfunction "2_2") (pintype "bidirectional"))
      (node (ref "RESET") (pin "A") (pinfunction "P_A") (pintype "passive"))
      (node (ref "RESET") (pin "A'") (pinfunction "P1_A'") (pintype "passive"))
      (node (ref "U1") (pin "COM1") (pinfunction "COM1_COM1") (pintype "bidirectional"))
      (node (ref "U1") (pin "COM2") (pinfunction "COM2_COM2") (pintype "bidirectional"))
      (node (ref "U1") (pin "COM3") (pinfunction "COM3_COM3") (pintype "bidirectional"))
      (node (ref "U1") (pin "COM4") (pinfunction "COM4_COM4") (pintype "bidirectional"))
      (node (ref "U2") (pin "2") (pinfunction "GND_2") (pintype "bidirectional"))
      (node (ref "U2") (pin "5") (pinfunction "DIR_5") (pintype "bidirectional"))
      (node (ref "U3") (pin "11") (pinfunction "V-_11") (pintype "power_in"))
      (node (ref "U5") (pin "1") (pinfunction "TEMP_1") (pintype "bidirectional"))
      (node (ref "U5") (pin "3") (pinfunction "GND_3") (pintype "bidirectional"))
      (node (ref "U5") (pin "GND1") (pinfunction "GND_GND1") (pintype "bidirectional"))
      (node (ref "UC1") (pin "P$12") (pinfunction "VSSA_P$12") (pintype "power_in"))
      (node (ref "UC1") (pin "P$18") (pinfunction "VSS_4_P$18") (pintype "power_in"))
      (node (ref "UC1") (pin "P$28") (pinfunction "PB2/BOOT1_P$28") (pintype "bidirectional"))
      (node (ref "UC1") (pin "P$31") (pinfunction "VSS_1_P$31") (pintype "power_in"))
      (node (ref "UC1") (pin "P$47") (pinfunction "VSS_2_P$47") (pintype "power_in"))
      (node (ref "UC1") (pin "P$63") (pinfunction "VSS_3_P$63") (pintype "power_in"))
    )
    (net (code "20") (name "GND2") (class "Default")
      (node (ref "C27") (pin "-") (pinfunction "2_-") (pintype "bidirectional"))
      (node (ref "C28") (pin "-") (pinfunction "2_-") (pintype "bidirectional"))
      (node (ref "C33") (pin "2") (pinfunction "2_2") (pintype "bidirectional"))
      (node (ref "L4") (pin "1") (pinfunction "1_1") (pintype "passive"))
      (node (ref "U11") (pin "2") (pinfunction "GND_2") (pintype "bidirectional"))
    )
    (net (code "21") (name "MICROPH") (class "Default")
      (node (ref "R9") (pin "1") (pinfunction "1_1") (pintype "bidirectional"))
      (node (ref "UC1") (pin "P$15") (pinfunction "PA1/USART2_RTS/ADC1/TIM2_CH2_P$15") (pintype "bidirectional"))
    )
    (net (code "22") (name "Net-(C6-Pad1)") (class "Default")
      (node (ref "C6") (pin "1") (pinfunction "1_1") (pintype "bidirectional"))
      (node (ref "M1") (pin "IN") (pinfunction "IN_IN") (pintype "bidirectional"))
      (node (ref "R13") (pin "1") (pinfunction "1_1") (pintype "bidirectional"))
    )
    (net (code "23") (name "Net-(C13-Pad2)") (class "Default")
      (node (ref "C13") (pin "2") (pinfunction "2_2") (pintype "bidirectional"))
      (node (ref "R21") (pin "1") (pinfunction "1_1") (pintype "bidirectional"))
    )
    (net (code "24") (name "Net-(C14-Pad1)") (class "Default")
      (node (ref "C14") (pin "1") (pinfunction "1_1") (pintype "bidirectional"))
      (node (ref "C17") (pin "2") (pinfunction "2_2") (pintype "bidirectional"))
      (node (ref "R10") (pin "2") (pinfunction "2_2") (pintype "bidirectional"))
      (node (ref "R8") (pin "2") (pinfunction "2_2") (pintype "bidirectional"))
    )
    (net (code "25") (name "Net-(C14-Pad2)") (class "Default")
      (node (ref "C14") (pin "2") (pinfunction "2_2") (pintype "bidirectional"))
      (node (ref "R17") (pin "1") (pinfunction "1_1") (pintype "bidirectional"))
    )
    (net (code "26") (name "Net-(C15-Pad2)") (class "Default")
      (node (ref "C15") (pin "2") (pinfunction "2_2") (pintype "bidirectional"))
      (node (ref "R17") (pin "2") (pinfunction "2_2") (pintype "bidirectional"))
      (node (ref "R26") (pin "1") (pinfunction "1_1") (pintype "bidirectional"))
    )
    (net (code "27") (name "Net-(C19-1)") (class "Default")
      (node (ref "C12") (pin "1") (pinfunction "1_1") (pintype "bidirectional"))
      (node (ref "C19") (pin "+") (pinfunction "1_+") (pintype "bidirectional"))
      (node (ref "R11") (pin "2") (pinfunction "2_2") (pintype "bidirectional"))
      (node (ref "R13") (pin "2") (pinfunction "2_2") (pintype "bidirectional"))
      (node (ref "R18") (pin "2") (pinfunction "2_2") (pintype "bidirectional"))
      (node (ref "R25") (pin "1") (pinfunction "1_1") (pintype "bidirectional"))
      (node (ref "U3") (pin "4") (pinfunction "V+_4") (pintype "power_in"))
    )
    (net (code "28") (name "Net-(C27-1)") (class "Default")
      (node (ref "C27") (pin "+") (pinfunction "1_+") (pintype "bidirectional"))
      (node (ref "C33") (pin "1") (pinfunction "1_1") (pintype "bidirectional"))
      (node (ref "L1") (pin "2") (pinfunction "2_2") (pintype "passive"))
      (node (ref "L3") (pin "2") (pinfunction "2_2") (pintype "passive"))
      (node (ref "U11") (pin "5") (pinfunction "VOUT_5") (pintype "bidirectional"))
    )
    (net (code "29") (name "Net-(C28-1)") (class "Default")
      (node (ref "C28") (pin "+") (pinfunction "1_+") (pintype "bidirectional"))
      (node (ref "L2") (pin "1") (pinfunction "1_1") (pintype "passive"))
      (node (ref "R41") (pin "2") (pinfunction "2_2") (pintype "bidirectional"))
      (node (ref "U11") (pin "4") (pinfunction "VIN_4") (pintype "bidirectional"))
    )
    (net (code "30") (name "Net-(D1-Pad-)") (class "Default")
      (node (ref "D1") (pin "-") (pinfunction "-_-") (pintype "passive"))
      (node (ref "R34") (pin "2") (pinfunction "2_2") (pintype "bidirectional"))
    )
    (net (code "31") (name "Net-(D2-Pad-)") (class "Default")
      (node (ref "D2") (pin "-") (pinfunction "-_-") (pintype "passive"))
      (node (ref "R35") (pin "2") (pinfunction "2_2") (pintype "bidirectional"))
    )
    (net (code "32") (name "Net-(D4-Pad+)") (class "Default")
      (node (ref "D4") (pin "+") (pinfunction "+_+") (pintype "passive"))
      (node (ref "R32") (pin "1") (pinfunction "1_1") (pintype "bidirectional"))
    )
    (net (code "33") (name "Net-(D5--)") (class "Default")
      (node (ref "D5") (pin "2") (pinfunction "-_2") (pintype "passive"))
      (node (ref "D6") (pin "1") (pinfunction "+_1") (pintype "passive"))
    )
    (net (code "34") (name "Net-(J1-Pad3)") (class "Default")
      (node (ref "J1") (pin "3") (pinfunction "3_3") (pintype "bidirectional"))
      (node (ref "J2") (pin "2") (pinfunction "2_2") (pintype "bidirectional"))
    )
    (net (code "35") (name "Net-(J2-Pad3)") (class "Default")
      (node (ref "J2") (pin "3") (pinfunction "3_3") (pintype "bidirectional"))
      (node (ref "J3") (pin "2") (pinfunction "2_2") (pintype "bidirectional"))
    )
    (net (code "36") (name "Net-(J3-Pad3)") (class "Default")
      (node (ref "J3") (pin "3") (pinfunction "3_3") (pintype "bidirectional"))
      (node (ref "J4") (pin "2") (pinfunction "2_2") (pintype "bidirectional"))
    )
    (net (code "37") (name "Net-(J4-Pad3)") (class "Default")
      (node (ref "J4") (pin "3") (pinfunction "3_3") (pintype "bidirectional"))
      (node (ref "J5") (pin "2") (pinfunction "2_2") (pintype "bidirectional"))
    )
    (net (code "38") (name "Net-(J5-Pad3)") (class "Default")
      (node (ref "J5") (pin "3") (pinfunction "3_3") (pintype "bidirectional"))
      (node (ref "J6") (pin "2") (pinfunction "2_2") (pintype "bidirectional"))
    )
    (net (code "39") (name "Net-(J6-Pad3)") (class "Default")
      (node (ref "J6") (pin "3") (pinfunction "3_3") (pintype "bidirectional"))
      (node (ref "J7") (pin "2") (pinfunction "2_2") (pintype "bidirectional"))
    )
    (net (code "40") (name "Net-(J7-Pad3)") (class "Default")
      (node (ref "J7") (pin "3") (pinfunction "3_3") (pintype "bidirectional"))
      (node (ref "J8") (pin "2") (pinfunction "2_2") (pintype "bidirectional"))
    )
    (net (code "41") (name "Net-(J8-Pad3)") (class "Default")
      (node (ref "J8") (pin "3") (pinfunction "3_3") (pintype "bidirectional"))
      (node (ref "J9") (pin "2") (pinfunction "2_2") (pintype "bidirectional"))
    )
    (net (code "42") (name "Net-(J10-Pad2)") (class "Default")
      (node (ref "J10") (pin "2") (pinfunction "2_2") (pintype "bidirectional"))
      (node (ref "J9") (pin "3") (pinfunction "3_3") (pintype "bidirectional"))
    )
    (net (code "43") (name "Net-(J10-Pad3)") (class "Default")
      (node (ref "J10") (pin "3") (pinfunction "3_3") (pintype "bidirectional"))
      (node (ref "J11") (pin "2") (pinfunction "2_2") (pintype "bidirectional"))
    )
    (net (code "44") (name "Net-(J11-Pad3)") (class "Default")
      (node (ref "J11") (pin "3") (pinfunction "3_3") (pintype "bidirectional"))
      (node (ref "J12") (pin "2") (pinfunction "2_2") (pintype "bidirectional"))
    )
    (net (code "45") (name "Net-(J12-Pad3)") (class "Default")
      (node (ref "J12") (pin "3") (pinfunction "3_3") (pintype "bidirectional"))
      (node (ref "J13") (pin "2") (pinfunction "2_2") (pintype "bidirectional"))
    )
    (net (code "46") (name "Net-(J13-Pad3)") (class "Default")
      (node (ref "J13") (pin "3") (pinfunction "3_3") (pintype "bidirectional"))
      (node (ref "J14") (pin "2") (pinfunction "2_2") (pintype "bidirectional"))
    )
    (net (code "47") (name "Net-(J14-Pad3)") (class "Default")
      (node (ref "J14") (pin "3") (pinfunction "3_3") (pintype "bidirectional"))
      (node (ref "J15") (pin "2") (pinfunction "2_2") (pintype "bidirectional"))
    )
    (net (code "48") (name "Net-(J15-Pad3)") (class "Default")
      (node (ref "J15") (pin "3") (pinfunction "3_3") (pintype "bidirectional"))
      (node (ref "J16") (pin "2") (pinfunction "2_2") (pintype "bidirectional"))
    )
    (net (code "49") (name "Net-(J16-Pad3)") (class "Default")
      (node (ref "J16") (pin "3") (pinfunction "3_3") (pintype "bidirectional"))
      (node (ref "J17") (pin "2") (pinfunction "2_2") (pintype "bidirectional"))
    )
    (net (code "50") (name "Net-(J17-Pad3)") (class "Default")
      (node (ref "J17") (pin "3") (pinfunction "3_3") (pintype "bidirectional"))
      (node (ref "J18") (pin "2") (pinfunction "2_2") (pintype "bidirectional"))
    )
    (net (code "51") (name "Net-(J18-Pad3)") (class "Default")
      (node (ref "J18") (pin "3") (pinfunction "3_3") (pintype "bidirectional"))
      (node (ref "J19") (pin "2") (pinfunction "2_2") (pintype "bidirectional"))
    )
    (net (code "52") (name "Net-(J19-Pad3)") (class "Default")
      (node (ref "J19") (pin "3") (pinfunction "3_3") (pintype "bidirectional"))
      (node (ref "J20") (pin "2") (pinfunction "2_2") (pintype "bidirectional"))
    )
    (net (code "53") (name "Net-(J20-Pad3)") (class "Default")
      (node (ref "J20") (pin "3") (pinfunction "3_3") (pintype "bidirectional"))
      (node (ref "J21") (pin "2") (pinfunction "2_2") (pintype "bidirectional"))
    )
    (net (code "54") (name "Net-(J21-Pad3)") (class "Default")
      (node (ref "J21") (pin "3") (pinfunction "3_3") (pintype "bidirectional"))
      (node (ref "J22") (pin "2") (pinfunction "2_2") (pintype "bidirectional"))
    )
    (net (code "55") (name "Net-(J22-Pad3)") (class "Default")
      (node (ref "J22") (pin "3") (pinfunction "3_3") (pintype "bidirectional"))
      (node (ref "J23") (pin "2") (pinfunction "2_2") (pintype "bidirectional"))
    )
    (net (code "56") (name "Net-(J23-Pad3)") (class "Default")
      (node (ref "J23") (pin "3") (pinfunction "3_3") (pintype "bidirectional"))
      (node (ref "J24") (pin "2") (pinfunction "2_2") (pintype "bidirectional"))
    )
    (net (code "57") (name "Net-(J24-Pad3)") (class "Default")
      (node (ref "J24") (pin "3") (pinfunction "3_3") (pintype "bidirectional"))
      (node (ref "J25") (pin "2") (pinfunction "2_2") (pintype "bidirectional"))
    )
    (net (code "58") (name "Net-(J25-Pad3)") (class "Default")
      (node (ref "J25") (pin "3") (pinfunction "3_3") (pintype "bidirectional"))
      (node (ref "J26") (pin "2") (pinfunction "2_2") (pintype "bidirectional"))
    )
    (net (code "59") (name "Net-(J26-Pad3)") (class "Default")
      (node (ref "J26") (pin "3") (pinfunction "3_3") (pintype "bidirectional"))
      (node (ref "J27") (pin "2") (pinfunction "2_2") (pintype "bidirectional"))
    )
    (net (code "60") (name "Net-(J27-Pad3)") (class "Default")
      (node (ref "J27") (pin "3") (pinfunction "3_3") (pintype "bidirectional"))
      (node (ref "J28") (pin "2") (pinfunction "2_2") (pintype "bidirectional"))
    )
    (net (code "61") (name "Net-(J28-Pad3)") (class "Default")
      (node (ref "J28") (pin "3") (pinfunction "3_3") (pintype "bidirectional"))
      (node (ref "J29") (pin "2") (pinfunction "2_2") (pintype "bidirectional"))
    )
    (net (code "62") (name "Net-(J29-Pad3)") (class "Default")
      (node (ref "J29") (pin "3") (pinfunction "3_3") (pintype "bidirectional"))
      (node (ref "J30") (pin "2") (pinfunction "2_2") (pintype "bidirectional"))
    )
    (net (code "63") (name "Net-(J30-Pad3)") (class "Default")
      (node (ref "J30") (pin "3") (pinfunction "3_3") (pintype "bidirectional"))
      (node (ref "J31") (pin "2") (pinfunction "2_2") (pintype "bidirectional"))
    )
    (net (code "64") (name "Net-(J31-Pad3)") (class "Default")
      (node (ref "J31") (pin "3") (pinfunction "3_3") (pintype "bidirectional"))
      (node (ref "J32") (pin "2") (pinfunction "2_2") (pintype "bidirectional"))
    )
    (net (code "65") (name "Net-(J32-Pad3)") (class "Default")
      (node (ref "J32") (pin "3") (pinfunction "3_3") (pintype "bidirectional"))
      (node (ref "J33") (pin "2") (pinfunction "2_2") (pintype "bidirectional"))
    )
    (net (code "66") (name "Net-(J33-Pad3)") (class "Default")
      (node (ref "J33") (pin "3") (pinfunction "3_3") (pintype "bidirectional"))
      (node (ref "J34") (pin "2") (pinfunction "2_2") (pintype "bidirectional"))
    )
    (net (code "67") (name "Net-(J34-Pad3)") (class "Default")
      (node (ref "J34") (pin "3") (pinfunction "3_3") (pintype "bidirectional"))
      (node (ref "J35") (pin "2") (pinfunction "2_2") (pintype "bidirectional"))
    )
    (net (code "68") (name "Net-(J35-Pad3)") (class "Default")
      (node (ref "J35") (pin "3") (pinfunction "3_3") (pintype "bidirectional"))
      (node (ref "J36") (pin "2") (pinfunction "2_2") (pintype "bidirectional"))
    )
    (net (code "69") (name "Net-(J38-D+)") (class "Default")
      (node (ref "J38") (pin "P3") (pinfunction "D+_P3") (pintype "bidirectional"))
      (node (ref "R7") (pin "1") (pinfunction "1_1") (pintype "bidirectional"))
    )
    (net (code "70") (name "Net-(J38-D-)") (class "Default")
      (node (ref "J38") (pin "P2") (pinfunction "D-_P2") (pintype "bidirectional"))
      (node (ref "R27") (pin "1") (pinfunction "1_1") (pintype "bidirectional"))
    )
    (net (code "71") (name "Net-(Q2-G)") (class "Default")
      (node (ref "Q2") (pin "1") (pinfunction "G_1") (pintype "passive"))
      (node (ref "Q4") (pin "3") (pinfunction "C_3") (pintype "passive"))
      (node (ref "R4") (pin "2") (pinfunction "2_2") (pintype "bidirectional"))
      (node (ref "R5") (pin "1") (pinfunction "1_1") (pintype "bidirectional"))
    )
    (net (code "72") (name "Net-(Q2-S)") (class "Default")
      (node (ref "Q2") (pin "2") (pinfunction "S_2") (pintype "passive"))
      (node (ref "Q4") (pin "1") (pinfunction "B_1") (pintype "passive"))
      (node (ref "R3") (pin "2") (pinfunction "2_2") (pintype "bidirectional"))
      (node (ref "R4") (pin "1") (pinfunction "1_1") (pintype "bidirectional"))
    )
    (net (code "73") (name "Net-(Q3-D)") (class "Default")
      (node (ref "Q3") (pin "3") (pinfunction "D_3") (pintype "passive"))
      (node (ref "R8") (pin "1") (pinfunction "1_1") (pintype "bidirectional"))
    )
    (net (code "74") (name "Net-(Q3-G)") (class "Default")
      (node (ref "C18") (pin "2") (pinfunction "2_2") (pintype "bidirectional"))
      (node (ref "Q3") (pin "1") (pinfunction "G_1") (pintype "passive"))
      (node (ref "R9") (pin "2") (pinfunction "2_2") (pintype "bidirectional"))
    )
    (net (code "75") (name "Net-(Q5-B)") (class "Default")
      (node (ref "Q5") (pin "1") (pinfunction "B_1") (pintype "passive"))
      (node (ref "R28") (pin "1") (pinfunction "1_1") (pintype "bidirectional"))
      (node (ref "R40") (pin "2") (pinfunction "2_2") (pintype "bidirectional"))
    )
    (net (code "76") (name "Net-(Q5-C)") (class "Default")
      (node (ref "Q5") (pin "3") (pinfunction "C_3") (pintype "passive"))
      (node (ref "Q6") (pin "1") (pinfunction "B_1") (pintype "passive"))
      (node (ref "R38") (pin "1") (pinfunction "1_1") (pintype "bidirectional"))
      (node (ref "R39") (pin "2") (pinfunction "2_2") (pintype "bidirectional"))
    )
    (net (code "77") (name "Net-(Q6-E)") (class "Default")
      (node (ref "Q6") (pin "2") (pinfunction "E_2") (pintype "passive"))
      (node (ref "R37") (pin "1") (pinfunction "1_1") (pintype "bidirectional"))
    )
    (net (code "78") (name "Net-(U2-A)") (class "Default")
      (node (ref "FB2") (pin "2") (pinfunction "2_2") (pintype "bidirectional"))
      (node (ref "U2") (pin "3") (pinfunction "A_3") (pintype "bidirectional"))
    )
    (net (code "79") (name "Net-(U3A-IN+)") (class "Default")
      (node (ref "C5") (pin "2") (pinfunction "2_2") (pintype "bidirectional"))
      (node (ref "R18") (pin "1") (pinfunction "1_1") (pintype "bidirectional"))
      (node (ref "R19") (pin "2") (pinfunction "2_2") (pintype "bidirectional"))
      (node (ref "U3") (pin "3") (pinfunction "IN+_3") (pintype "input"))
    )
    (net (code "80") (name "Net-(U3B-IN-)") (class "Default")
      (node (ref "C6") (pin "2") (pinfunction "2_2") (pintype "bidirectional"))
      (node (ref "R20") (pin "1") (pinfunction "1_1") (pintype "bidirectional"))
      (node (ref "U3") (pin "9") (pinfunction "IN-_9") (pintype "input"))
    )
    (net (code "81") (name "Net-(U3B-OUT)") (class "Default")
      (node (ref "C13") (pin "1") (pinfunction "1_1") (pintype "bidirectional"))
      (node (ref "R20") (pin "2") (pinfunction "2_2") (pintype "bidirectional"))
      (node (ref "U3") (pin "8") (pinfunction "OUT_8") (pintype "output"))
    )
    (net (code "82") (name "Net-(U3C-IN-)") (class "Default")
      (node (ref "R21") (pin "2") (pinfunction "2_2") (pintype "bidirectional"))
      (node (ref "R22") (pin "1") (pinfunction "1_1") (pintype "bidirectional"))
      (node (ref "U3") (pin "6") (pinfunction "IN-_6") (pintype "input"))
    )
    (net (code "83") (name "Net-(U3C-OUT)") (class "Default")
      (node (ref "C17") (pin "1") (pinfunction "1_1") (pintype "bidirectional"))
      (node (ref "R22") (pin "2") (pinfunction "2_2") (pintype "bidirectional"))
      (node (ref "U3") (pin "7") (pinfunction "OUT_7") (pintype "output"))
    )
    (net (code "84") (name "Net-(U3D-IN-)") (class "Default")
      (node (ref "C16") (pin "2") (pinfunction "2_2") (pintype "bidirectional"))
      (node (ref "R23") (pin "1") (pinfunction "1_1") (pintype "bidirectional"))
      (node (ref "R24") (pin "1") (pinfunction "1_1") (pintype "bidirectional"))
      (node (ref "R26") (pin "2") (pinfunction "2_2") (pintype "bidirectional"))
      (node (ref "U3") (pin "13") (pinfunction "IN-_13") (pintype "input"))
    )
    (net (code "85") (name "Net-(U3D-OUT)") (class "Default")
      (node (ref "C7") (pin "1") (pinfunction "1_1") (pintype "bidirectional"))
      (node (ref "R23") (pin "2") (pinfunction "2_2") (pintype "bidirectional"))
      (node (ref "U3") (pin "14") (pinfunction "OUT_14") (pintype "output"))
    )
    (net (code "86") (name "Net-(U5-PROG)") (class "Default")
      (node (ref "R36") (pin "2") (pinfunction "2_2") (pintype "bidirectional"))
      (node (ref "U5") (pin "2") (pinfunction "PROG_2") (pintype "bidirectional"))
    )
    (net (code "87") (name "Net-(U5-~{CHRG})") (class "Default")
      (node (ref "R34") (pin "1") (pinfunction "1_1") (pintype "bidirectional"))
      (node (ref "U5") (pin "7") (pinfunction "~{CHRG}_7") (pintype "bidirectional"))
    )
    (net (code "88") (name "Net-(U5-~{STDBY})") (class "Default")
      (node (ref "R35") (pin "1") (pinfunction "1_1") (pintype "bidirectional"))
      (node (ref "U5") (pin "6") (pinfunction "~{STDBY}_6") (pintype "bidirectional"))
    )
    (net (code "89") (name "Net-(U11-EN)") (class "Default")
      (node (ref "R41") (pin "1") (pinfunction "1_1") (pintype "bidirectional"))
      (node (ref "U11") (pin "1") (pinfunction "EN_1") (pintype "bidirectional"))
    )
    (net (code "90") (name "Net-(U11-LX)") (class "Default")
      (node (ref "L1") (pin "1") (pinfunction "1_1") (pintype "passive"))
      (node (ref "U11") (pin "3") (pinfunction "LX_3") (pintype "bidirectional"))
    )
    (net (code "91") (name "Net-(UC1-PA5{slash}SPI1_SCK{slash}ADC5)") (class "Default")
      (node (ref "R32") (pin "2") (pinfunction "2_2") (pintype "bidirectional"))
      (node (ref "UC1") (pin "P$21") (pinfunction "PA5/SPI1_SCK/ADC5_P$21") (pintype "bidirectional"))
    )
    (net (code "92") (name "Net-(UC1-PB0{slash}ADC8{slash}TIM3_CH3)") (class "Default")
      (node (ref "FB1") (pin "2") (pinfunction "2_2") (pintype "bidirectional"))
      (node (ref "UC1") (pin "P$26") (pinfunction "PB0/ADC8/TIM3_CH3_P$26") (pintype "bidirectional"))
    )
    (net (code "93") (name "Net-(UC1-PC0{slash}ADC10)") (class "Default")
      (node (ref "R29") (pin "2") (pinfunction "2_2") (pintype "bidirectional"))
      (node (ref "UC1") (pin "P$8") (pinfunction "PC0/ADC10_P$8") (pintype "bidirectional"))
    )
    (net (code "94") (name "Net-(UC1-PC1{slash}ADC11)") (class "Default")
      (node (ref "R31") (pin "1") (pinfunction "1_1") (pintype "bidirectional"))
      (node (ref "UC1") (pin "P$9") (pinfunction "PC1/ADC11_P$9") (pintype "bidirectional"))
    )
    (net (code "95") (name "Net-(UC1-PC2{slash}ADC12)") (class "Default")
      (node (ref "R30") (pin "1") (pinfunction "1_1") (pintype "bidirectional"))
      (node (ref "UC1") (pin "P$10") (pinfunction "PC2/ADC12_P$10") (pintype "bidirectional"))
    )
    (net (code "96") (name "Net-(UC1-PC3{slash}ADC13)") (class "Default")
      (node (ref "R14") (pin "2") (pinfunction "2_2") (pintype "bidirectional"))
      (node (ref "R15") (pin "1") (pinfunction "1_1") (pintype "bidirectional"))
      (node (ref "UC1") (pin "P$11") (pinfunction "PC3/ADC13_P$11") (pintype "bidirectional"))
    )
    (net (code "97") (name "Net-(UC1-PD0{slash}OSC_IN)") (class "Default")
      (node (ref "C2") (pin "2") (pinfunction "2_2") (pintype "bidirectional"))
      (node (ref "UC1") (pin "P$5") (pinfunction "PD0/OSC_IN_P$5") (pintype "bidirectional"))
      (node (ref "X1") (pin "2") (pinfunction "2_2") (pintype "passive"))
    )
    (net (code "98") (name "Net-(UC1-PD1{slash}OSC_OUT)") (class "Default")
      (node (ref "C20") (pin "2") (pinfunction "2_2") (pintype "bidirectional"))
      (node (ref "UC1") (pin "P$6") (pinfunction "PD1/OSC_OUT_P$6") (pintype "bidirectional"))
      (node (ref "X1") (pin "1") (pinfunction "1_1") (pintype "passive"))
    )
    (net (code "99") (name "REF") (class "Default")
      (node (ref "R24") (pin "2") (pinfunction "2_2") (pintype "bidirectional"))
      (node (ref "U3") (pin "1") (pinfunction "OUT_1") (pintype "output"))
      (node (ref "U3") (pin "10") (pinfunction "IN+_10") (pintype "input"))
      (node (ref "U3") (pin "12") (pinfunction "IN+_12") (pintype "input"))
      (node (ref "U3") (pin "2") (pinfunction "IN-_2") (pintype "input"))
      (node (ref "U3") (pin "5") (pinfunction "IN+_5") (pintype "input"))
    )
    (net (code "100") (name "SOUND") (class "Default")
      (node (ref "C7") (pin "2") (pinfunction "2_2") (pintype "bidirectional"))
      (node (ref "R11") (pin "1") (pinfunction "1_1") (pintype "bidirectional"))
      (node (ref "R12") (pin "2") (pinfunction "2_2") (pintype "bidirectional"))
      (node (ref "UC1") (pin "P$16") (pinfunction "PA2/USART2_TX/ADC2/TIM2_CH3_P$16") (pintype "bidirectional"))
    )
    (net (code "101") (name "V+") (class "Default")
      (node (ref "C1") (pin "+") (pinfunction "1_+") (pintype "bidirectional"))
      (node (ref "C3") (pin "2") (pinfunction "2_2") (pintype "bidirectional"))
      (node (ref "C34") (pin "1") (pinfunction "1_1") (pintype "bidirectional"))
      (node (ref "C35") (pin "1") (pinfunction "1_1") (pintype "bidirectional"))
      (node (ref "C36") (pin "1") (pinfunction "1_1") (pintype "bidirectional"))
      (node (ref "C37") (pin "1") (pinfunction "1_1") (pintype "bidirectional"))
      (node (ref "C38") (pin "1") (pinfunction "1_1") (pintype "bidirectional"))
      (node (ref "C39") (pin "1") (pinfunction "1_1") (pintype "bidirectional"))
      (node (ref "C4") (pin "1") (pinfunction "1_1") (pintype "bidirectional"))
      (node (ref "J1") (pin "1") (pinfunction "1_1") (pintype "bidirectional"))
      (node (ref "J10") (pin "1") (pinfunction "1_1") (pintype "bidirectional"))
      (node (ref "J11") (pin "1") (pinfunction "1_1") (pintype "bidirectional"))
      (node (ref "J12") (pin "1") (pinfunction "1_1") (pintype "bidirectional"))
      (node (ref "J13") (pin "1") (pinfunction "1_1") (pintype "bidirectional"))
      (node (ref "J14") (pin "1") (pinfunction "1_1") (pintype "bidirectional"))
      (node (ref "J15") (pin "1") (pinfunction "1_1") (pintype "bidirectional"))
      (node (ref "J16") (pin "1") (pinfunction "1_1") (pintype "bidirectional"))
      (node (ref "J17") (pin "1") (pinfunction "1_1") (pintype "bidirectional"))
      (node (ref "J18") (pin "1") (pinfunction "1_1") (pintype "bidirectional"))
      (node (ref "J19") (pin "1") (pinfunction "1_1") (pintype "bidirectional"))
      (node (ref "J2") (pin "1") (pinfunction "1_1") (pintype "bidirectional"))
      (node (ref "J20") (pin "1") (pinfunction "1_1") (pintype "bidirectional"))
      (node (ref "J21") (pin "1") (pinfunction "1_1") (pintype "bidirectional"))
      (node (ref "J22") (pin "1") (pinfunction "1_1") (pintype "bidirectional"))
      (node (ref "J23") (pin "1") (pinfunction "1_1") (pintype "bidirectional"))
      (node (ref "J24") (pin "1") (pinfunction "1_1") (pintype "bidirectional"))
      (node (ref "J25") (pin "1") (pinfunction "1_1") (pintype "bidirectional"))
      (node (ref "J26") (pin "1") (pinfunction "1_1") (pintype "bidirectional"))
      (node (ref "J27") (pin "1") (pinfunction "1_1") (pintype "bidirectional"))
      (node (ref "J28") (pin "1") (pinfunction "1_1") (pintype "bidirectional"))
      (node (ref "J29") (pin "1") (pinfunction "1_1") (pintype "bidirectional"))
      (node (ref "J3") (pin "1") (pinfunction "1_1") (pintype "bidirectional"))
      (node (ref "J30") (pin "1") (pinfunction "1_1") (pintype "bidirectional"))
      (node (ref "J31") (pin "1") (pinfunction "1_1") (pintype "bidirectional"))
      (node (ref "J32") (pin "1") (pinfunction "1_1") (pintype "bidirectional"))
      (node (ref "J33") (pin "1") (pinfunction "1_1") (pintype "bidirectional"))
      (node (ref "J34") (pin "1") (pinfunction "1_1") (pintype "bidirectional"))
      (node (ref "J35") (pin "1") (pinfunction "1_1") (pintype "bidirectional"))
      (node (ref "J36") (pin "1") (pinfunction "1_1") (pintype "bidirectional"))
      (node (ref "J4") (pin "1") (pinfunction "1_1") (pintype "bidirectional"))
      (node (ref "J5") (pin "1") (pinfunction "1_1") (pintype "bidirectional"))
      (node (ref "J6") (pin "1") (pinfunction "1_1") (pintype "bidirectional"))
      (node (ref "J7") (pin "1") (pinfunction "1_1") (pintype "bidirectional"))
      (node (ref "J8") (pin "1") (pinfunction "1_1") (pintype "bidirectional"))
      (node (ref "J9") (pin "1") (pinfunction "1_1") (pintype "bidirectional"))
      (node (ref "Q2") (pin "3") (pinfunction "D_3") (pintype "passive"))
      (node (ref "R14") (pin "1") (pinfunction "1_1") (pintype "bidirectional"))
    )
    (net (code "102") (name "VBAT") (class "Default")
      (node (ref "B1") (pin "+") (pinfunction "+_+") (pintype "bidirectional"))
      (node (ref "C30") (pin "+") (pinfunction "1_+") (pintype "bidirectional"))
      (node (ref "D3") (pin "+") (pinfunction "+_+") (pintype "passive"))
      (node (ref "U5") (pin "5") (pinfunction "BAT_5") (pintype "bidirectional"))
    )
    (net (code "103") (name "XOUT") (class "Default")
      (node (ref "C11") (pin "2") (pinfunction "2_2") (pintype "bidirectional"))
      (node (ref "U1") (pin "X") (pinfunction "X_X") (pintype "bidirectional"))
      (node (ref "UC1") (pin "P$20") (pinfunction "PA4/SPI1_NSS/USART2_CK/ADC4_P$20") (pintype "bidirectional"))
    )
    (net (code "104") (name "YOUT") (class "Default")
      (node (ref "C10") (pin "2") (pinfunction "2_2") (pintype "bidirectional"))
      (node (ref "U1") (pin "Y") (pinfunction "Y_Y") (pintype "bidirectional"))
      (node (ref "UC1") (pin "P$22") (pinfunction "PA6/SPI1_MISO/ADC6/TIM3_CH1_P$22") (pintype "bidirectional"))
    )
    (net (code "105") (name "ZOUT") (class "Default")
      (node (ref "C9") (pin "2") (pinfunction "2_2") (pintype "bidirectional"))
      (node (ref "U1") (pin "Z") (pinfunction "Z_Z") (pintype "bidirectional"))
      (node (ref "UC1") (pin "P$23") (pinfunction "PA7/SPI1_MOSI/ADC7/TIM3_CH2_P$23") (pintype "bidirectional"))
    )
    (net (code "106") (name "unconnected-(J36-Pad3)") (class "Default")
      (node (ref "J36") (pin "3") (pinfunction "3_3") (pintype "bidirectional"))
    )
    (net (code "107") (name "unconnected-(J37-Pad1)") (class "Default")
      (node (ref "J37") (pin "1") (pinfunction "1_1") (pintype "bidirectional"))
    )
    (net (code "108") (name "unconnected-(J38-ID-PadP4)") (class "Default")
      (node (ref "J38") (pin "P4") (pinfunction "ID_P4") (pintype "bidirectional"))
    )
    (net (code "109") (name "unconnected-(SW3-PadCH1B)") (class "Default")
      (node (ref "SW3") (pin "CH1B") (pinfunction "CH1B_CH1B") (pintype "bidirectional"))
    )
    (net (code "110") (name "unconnected-(SW3-PadCH2B)") (class "Default")
      (node (ref "SW3") (pin "CH2B") (pinfunction "CH2B_CH2B") (pintype "bidirectional"))
    )
    (net (code "111") (name "unconnected-(U$2-PadP$1)") (class "Default")
      (node (ref "U$2") (pin "P$1") (pinfunction "P$1_P$1") (pintype "bidirectional"))
    )
    (net (code "112") (name "unconnected-(U$3-PadP$1)") (class "Default")
      (node (ref "U$3") (pin "P$1") (pinfunction "P$1_P$1") (pintype "bidirectional"))
    )
    (net (code "113") (name "unconnected-(U1-PadNC1)") (class "Default")
      (node (ref "U1") (pin "NC1") (pinfunction "NC1_NC1") (pintype "bidirectional"))
    )
    (net (code "114") (name "unconnected-(U1-PadNC2)") (class "Default")
      (node (ref "U1") (pin "NC2") (pinfunction "NC2_NC2") (pintype "bidirectional"))
    )
    (net (code "115") (name "unconnected-(U1-PadNC3)") (class "Default")
      (node (ref "U1") (pin "NC3") (pinfunction "NC3_NC3") (pintype "bidirectional"))
    )
    (net (code "116") (name "unconnected-(U1-PadNC4)") (class "Default")
      (node (ref "U1") (pin "NC4") (pinfunction "NC4_NC4") (pintype "bidirectional"))
    )
    (net (code "117") (name "unconnected-(U1-PadNC5)") (class "Default")
      (node (ref "U1") (pin "NC5") (pinfunction "NC5_NC5") (pintype "bidirectional"))
    )
    (net (code "118") (name "unconnected-(U1-PadNC6)") (class "Default")
      (node (ref "U1") (pin "NC6") (pinfunction "NC6_NC6") (pintype "bidirectional"))
    )
    (net (code "119") (name "unconnected-(U1-PadST)") (class "Default")
      (node (ref "U1") (pin "ST") (pinfunction "ST_ST") (pintype "bidirectional"))
    )
    (net (code "120") (name "unconnected-(UC1-PA0-WKUP{slash}USART2_CTS{slash}ADC0{slash}TIM2_CH1_ETR-PadP$14)") (class "Default")
      (node (ref "UC1") (pin "P$14") (pinfunction "PA0-WKUP/USART2_CTS/ADC0/TIM2_CH1_ETR_P$14") (pintype "bidirectional"))
    )
    (net (code "121") (name "unconnected-(UC1-PA3{slash}USART2_RX{slash}ADC3{slash}TIM2_CH4-PadP$17)") (class "Default")
      (node (ref "UC1") (pin "P$17") (pinfunction "PA3/USART2_RX/ADC3/TIM2_CH4_P$17") (pintype "bidirectional"))
    )
    (net (code "122") (name "unconnected-(UC1-PA8{slash}USART1_CK{slash}TIM1_CH1{slash}MCO-PadP$41)") (class "Default")
      (node (ref "UC1") (pin "P$41") (pinfunction "PA8/USART1_CK/TIM1_CH1/MCO_P$41") (pintype "bidirectional"))
    )
    (net (code "123") (name "unconnected-(UC1-PB1{slash}ADC9{slash}TIM3_CH4-PadP$27)") (class "Default")
      (node (ref "UC1") (pin "P$27") (pinfunction "PB1/ADC9/TIM3_CH4_P$27") (pintype "bidirectional"))
    )
    (net (code "124") (name "unconnected-(UC1-PB5{slash}I2C1_SMBA-PadP$57)") (class "Default")
      (node (ref "UC1") (pin "P$57") (pinfunction "PB5/I2C1_SMBA_P$57") (pintype "bidirectional"))
    )
    (net (code "125") (name "unconnected-(UC1-PB6{slash}I2C1_SCL{slash}TIM4_CH1-PadP$58)") (class "Default")
      (node (ref "UC1") (pin "P$58") (pinfunction "PB6/I2C1_SCL/TIM4_CH1_P$58") (pintype "bidirectional"))
    )
    (net (code "126") (name "unconnected-(UC1-PB7{slash}I2C1_SDA{slash}TIM4_CH2-PadP$59)") (class "Default")
      (node (ref "UC1") (pin "P$59") (pinfunction "PB7/I2C1_SDA/TIM4_CH2_P$59") (pintype "bidirectional"))
    )
    (net (code "127") (name "unconnected-(UC1-PB8{slash}TIM4_CH3-PadP$61)") (class "Default")
      (node (ref "UC1") (pin "P$61") (pinfunction "PB8/TIM4_CH3_P$61") (pintype "bidirectional"))
    )
    (net (code "128") (name "unconnected-(UC1-PB9{slash}TIM4_CH4-PadP$62)") (class "Default")
      (node (ref "UC1") (pin "P$62") (pinfunction "PB9/TIM4_CH4_P$62") (pintype "bidirectional"))
    )
    (net (code "129") (name "unconnected-(UC1-PB10{slash}I2C2_SCL{slash}USART3_TX-PadP$29)") (class "Default")
      (node (ref "UC1") (pin "P$29") (pinfunction "PB10/I2C2_SCL/USART3_TX_P$29") (pintype "bidirectional"))
    )
    (net (code "130") (name "unconnected-(UC1-PB11{slash}I2C2_SDA{slash}USART3_RX-PadP$30)") (class "Default")
      (node (ref "UC1") (pin "P$30") (pinfunction "PB11/I2C2_SDA/USART3_RX_P$30") (pintype "bidirectional"))
    )
    (net (code "131") (name "unconnected-(UC1-PB12{slash}SPI2_NSS{slash}I2C2_SMBAL{slash}USART3_CK{slash}TIM1_BKIN-PadP$33)") (class "Default")
      (node (ref "UC1") (pin "P$33") (pinfunction "PB12/SPI2_NSS/I2C2_SMBAL/USART3_CK/TIM1_BKIN_P$33") (pintype "bidirectional"))
    )
    (net (code "132") (name "unconnected-(UC1-PB13{slash}SPI2_SCK{slash}USART3_CTS{slash}TIM1_CH1N-PadP$34)") (class "Default")
      (node (ref "UC1") (pin "P$34") (pinfunction "PB13/SPI2_SCK/USART3_CTS/TIM1_CH1N_P$34") (pintype "bidirectional"))
    )
    (net (code "133") (name "unconnected-(UC1-PB14{slash}SPI2_MISO{slash}USART3_RTS{slash}TIM1_CH2N-PadP$35)") (class "Default")
      (node (ref "UC1") (pin "P$35") (pinfunction "PB14/SPI2_MISO/USART3_RTS/TIM1_CH2N_P$35") (pintype "bidirectional"))
    )
    (net (code "134") (name "unconnected-(UC1-PB15{slash}SPI2_MOSI{slash}TIM1_CH3N-PadP$36)") (class "Default")
      (node (ref "UC1") (pin "P$36") (pinfunction "PB15/SPI2_MOSI/TIM1_CH3N_P$36") (pintype "bidirectional"))
    )
    (net (code "135") (name "unconnected-(UC1-PC4{slash}ADC14-PadP$24)") (class "Default")
      (node (ref "UC1") (pin "P$24") (pinfunction "PC4/ADC14_P$24") (pintype "bidirectional"))
    )
    (net (code "136") (name "unconnected-(UC1-PC5{slash}ADC15-PadP$25)") (class "Default")
      (node (ref "UC1") (pin "P$25") (pinfunction "PC5/ADC15_P$25") (pintype "bidirectional"))
    )
    (net (code "137") (name "unconnected-(UC1-PC6-PadP$37)") (class "Default")
      (node (ref "UC1") (pin "P$37") (pinfunction "PC6_P$37") (pintype "bidirectional"))
    )
    (net (code "138") (name "unconnected-(UC1-PC7-PadP$38)") (class "Default")
      (node (ref "UC1") (pin "P$38") (pinfunction "PC7_P$38") (pintype "bidirectional"))
    )
    (net (code "139") (name "unconnected-(UC1-PC8-PadP$39)") (class "Default")
      (node (ref "UC1") (pin "P$39") (pinfunction "PC8_P$39") (pintype "bidirectional"))
    )
    (net (code "140") (name "unconnected-(UC1-PC10-PadP$51)") (class "Default")
      (node (ref "UC1") (pin "P$51") (pinfunction "PC10_P$51") (pintype "bidirectional"))
    )
    (net (code "141") (name "unconnected-(UC1-PC13-TAMPER-RTC-PadP$2)") (class "Default")
      (node (ref "UC1") (pin "P$2") (pinfunction "PC13-TAMPER-RTC_P$2") (pintype "bidirectional"))
    )
    (net (code "142") (name "unconnected-(UC1-PC14{slash}OSC32_IN-PadP$3)") (class "Default")
      (node (ref "UC1") (pin "P$3") (pinfunction "PC14/OSC32_IN_P$3") (pintype "bidirectional"))
    )
    (net (code "143") (name "unconnected-(UC1-PC15{slash}OSC_OUT-PadP$4)") (class "Default")
      (node (ref "UC1") (pin "P$4") (pinfunction "PC15/OSC_OUT_P$4") (pintype "bidirectional"))
    )
    (net (code "144") (name "unconnected-(UC1-PD2{slash}TIM3-ETR-PadP$54)") (class "Default")
      (node (ref "UC1") (pin "P$54") (pinfunction "PD2/TIM3-ETR_P$54") (pintype "bidirectional"))
    )
  )
)
